# Alcohol_Detector_Project_Schematic.net
KiCad netlist of a schematic drawn in EAGLE
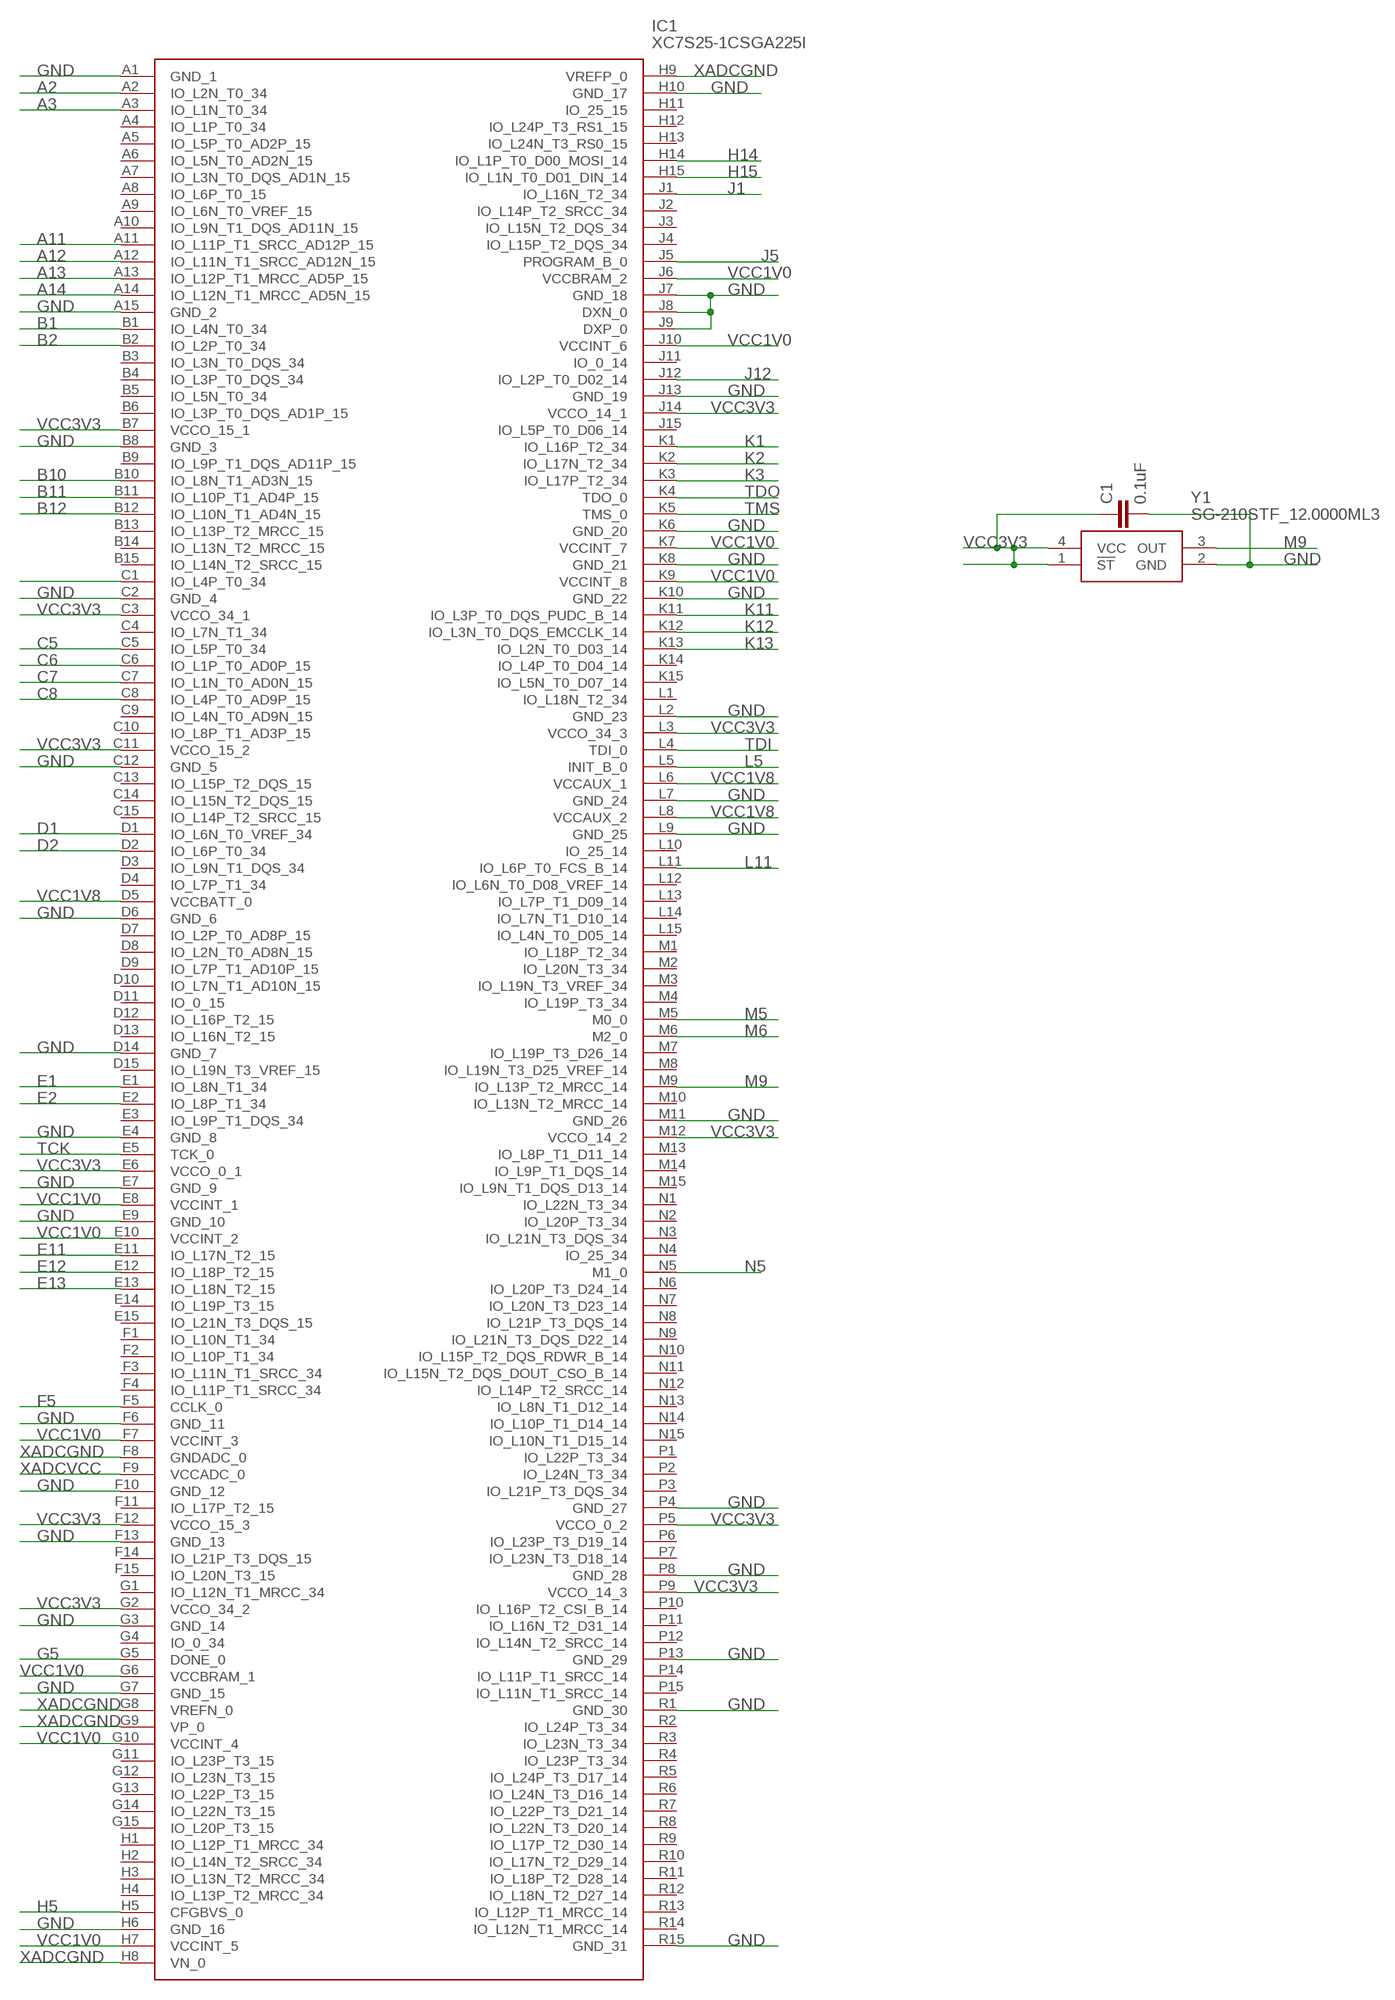
[diagram p0: schematic, sheet 1]
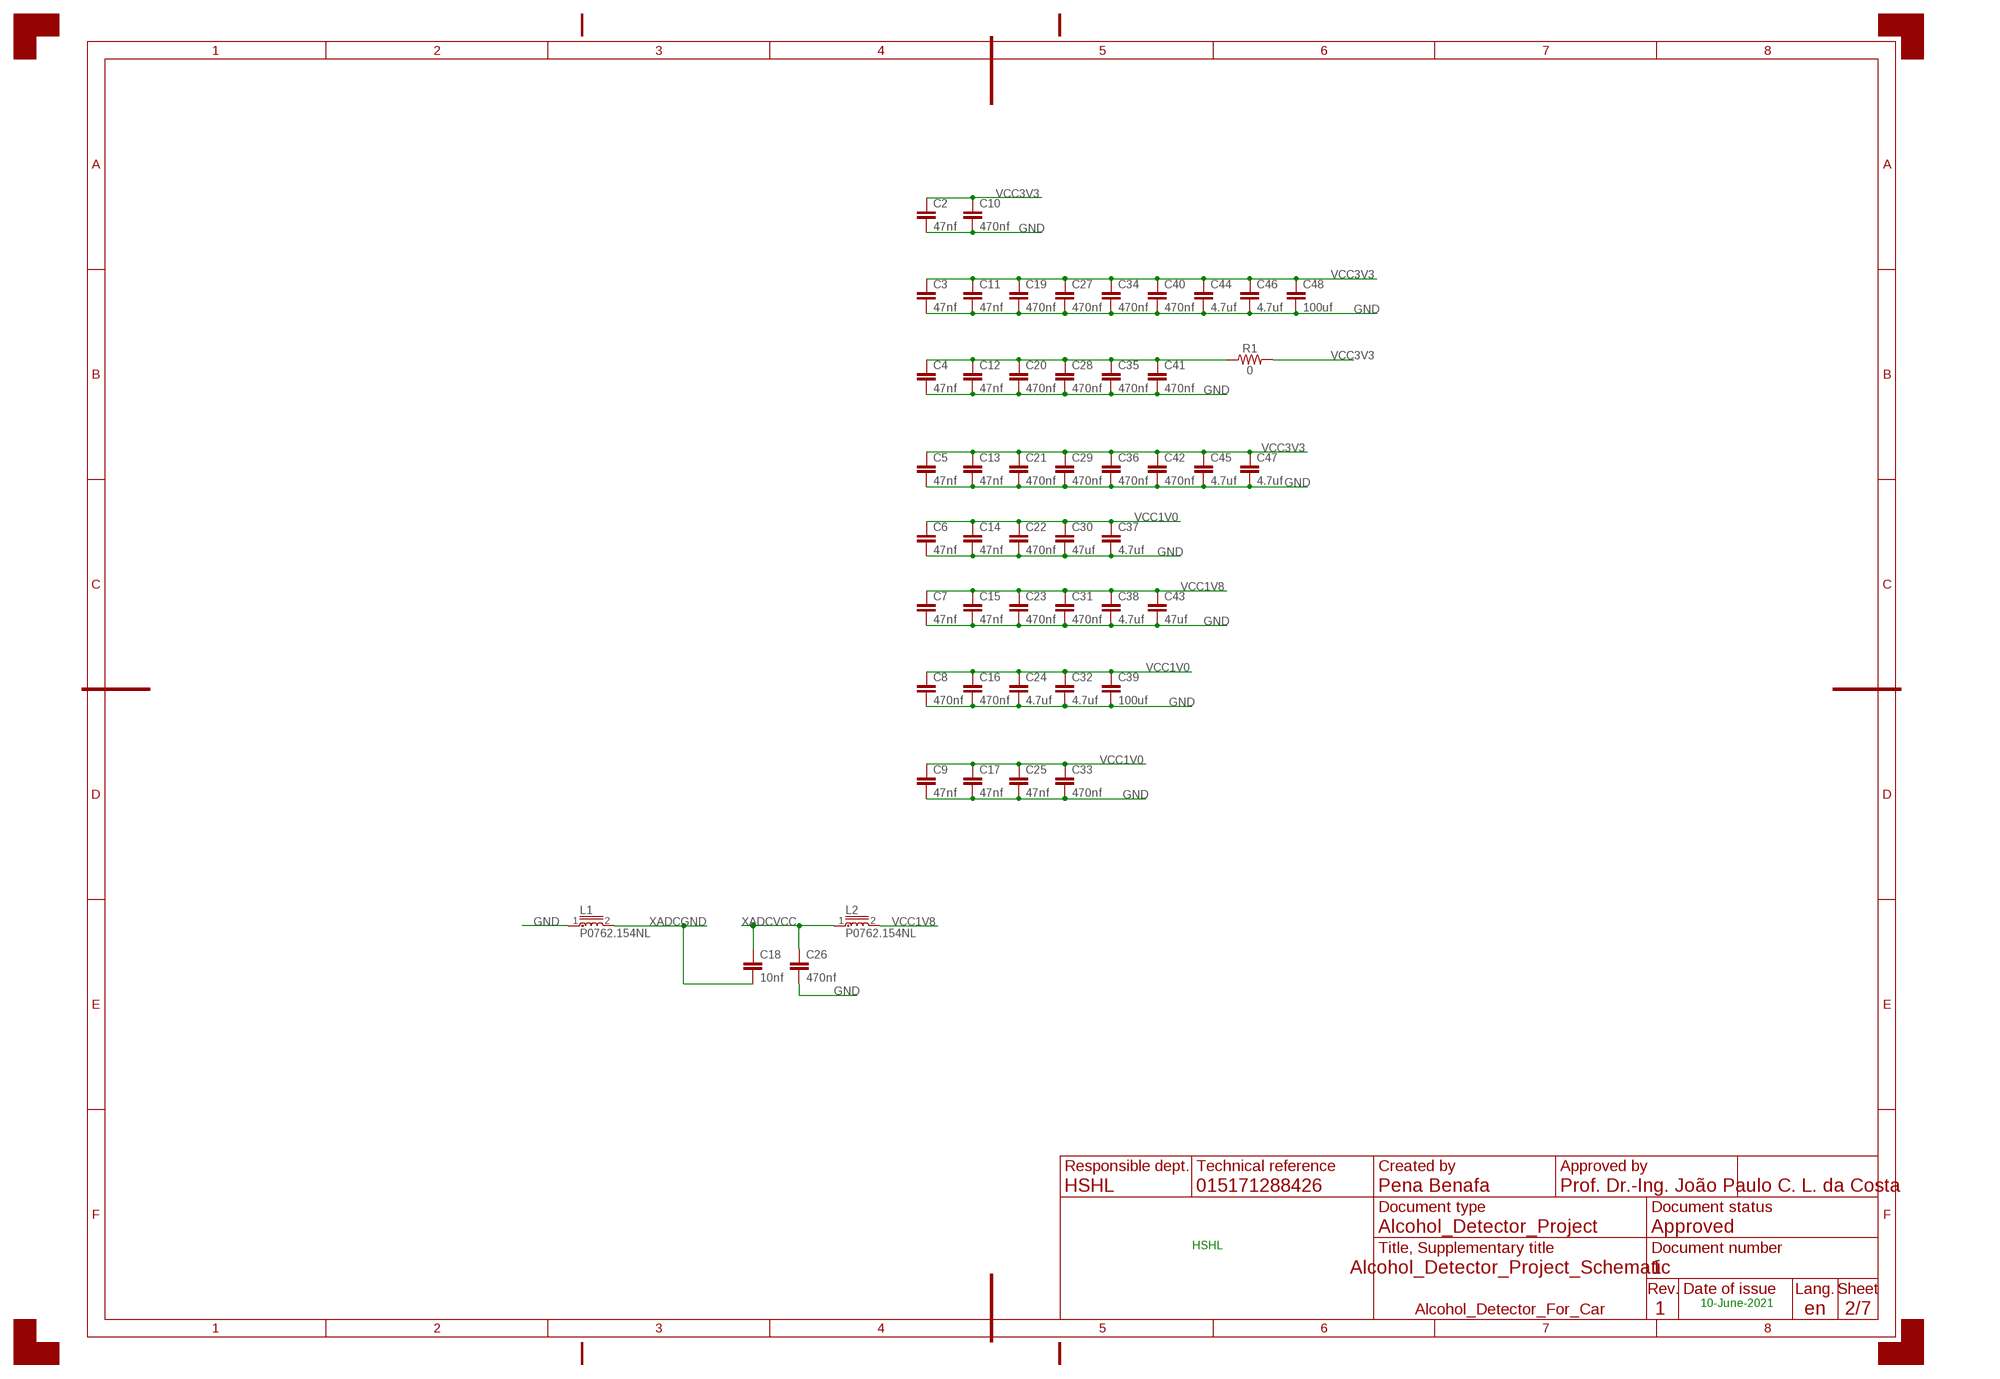
[diagram p1: schematic, sheet 2]
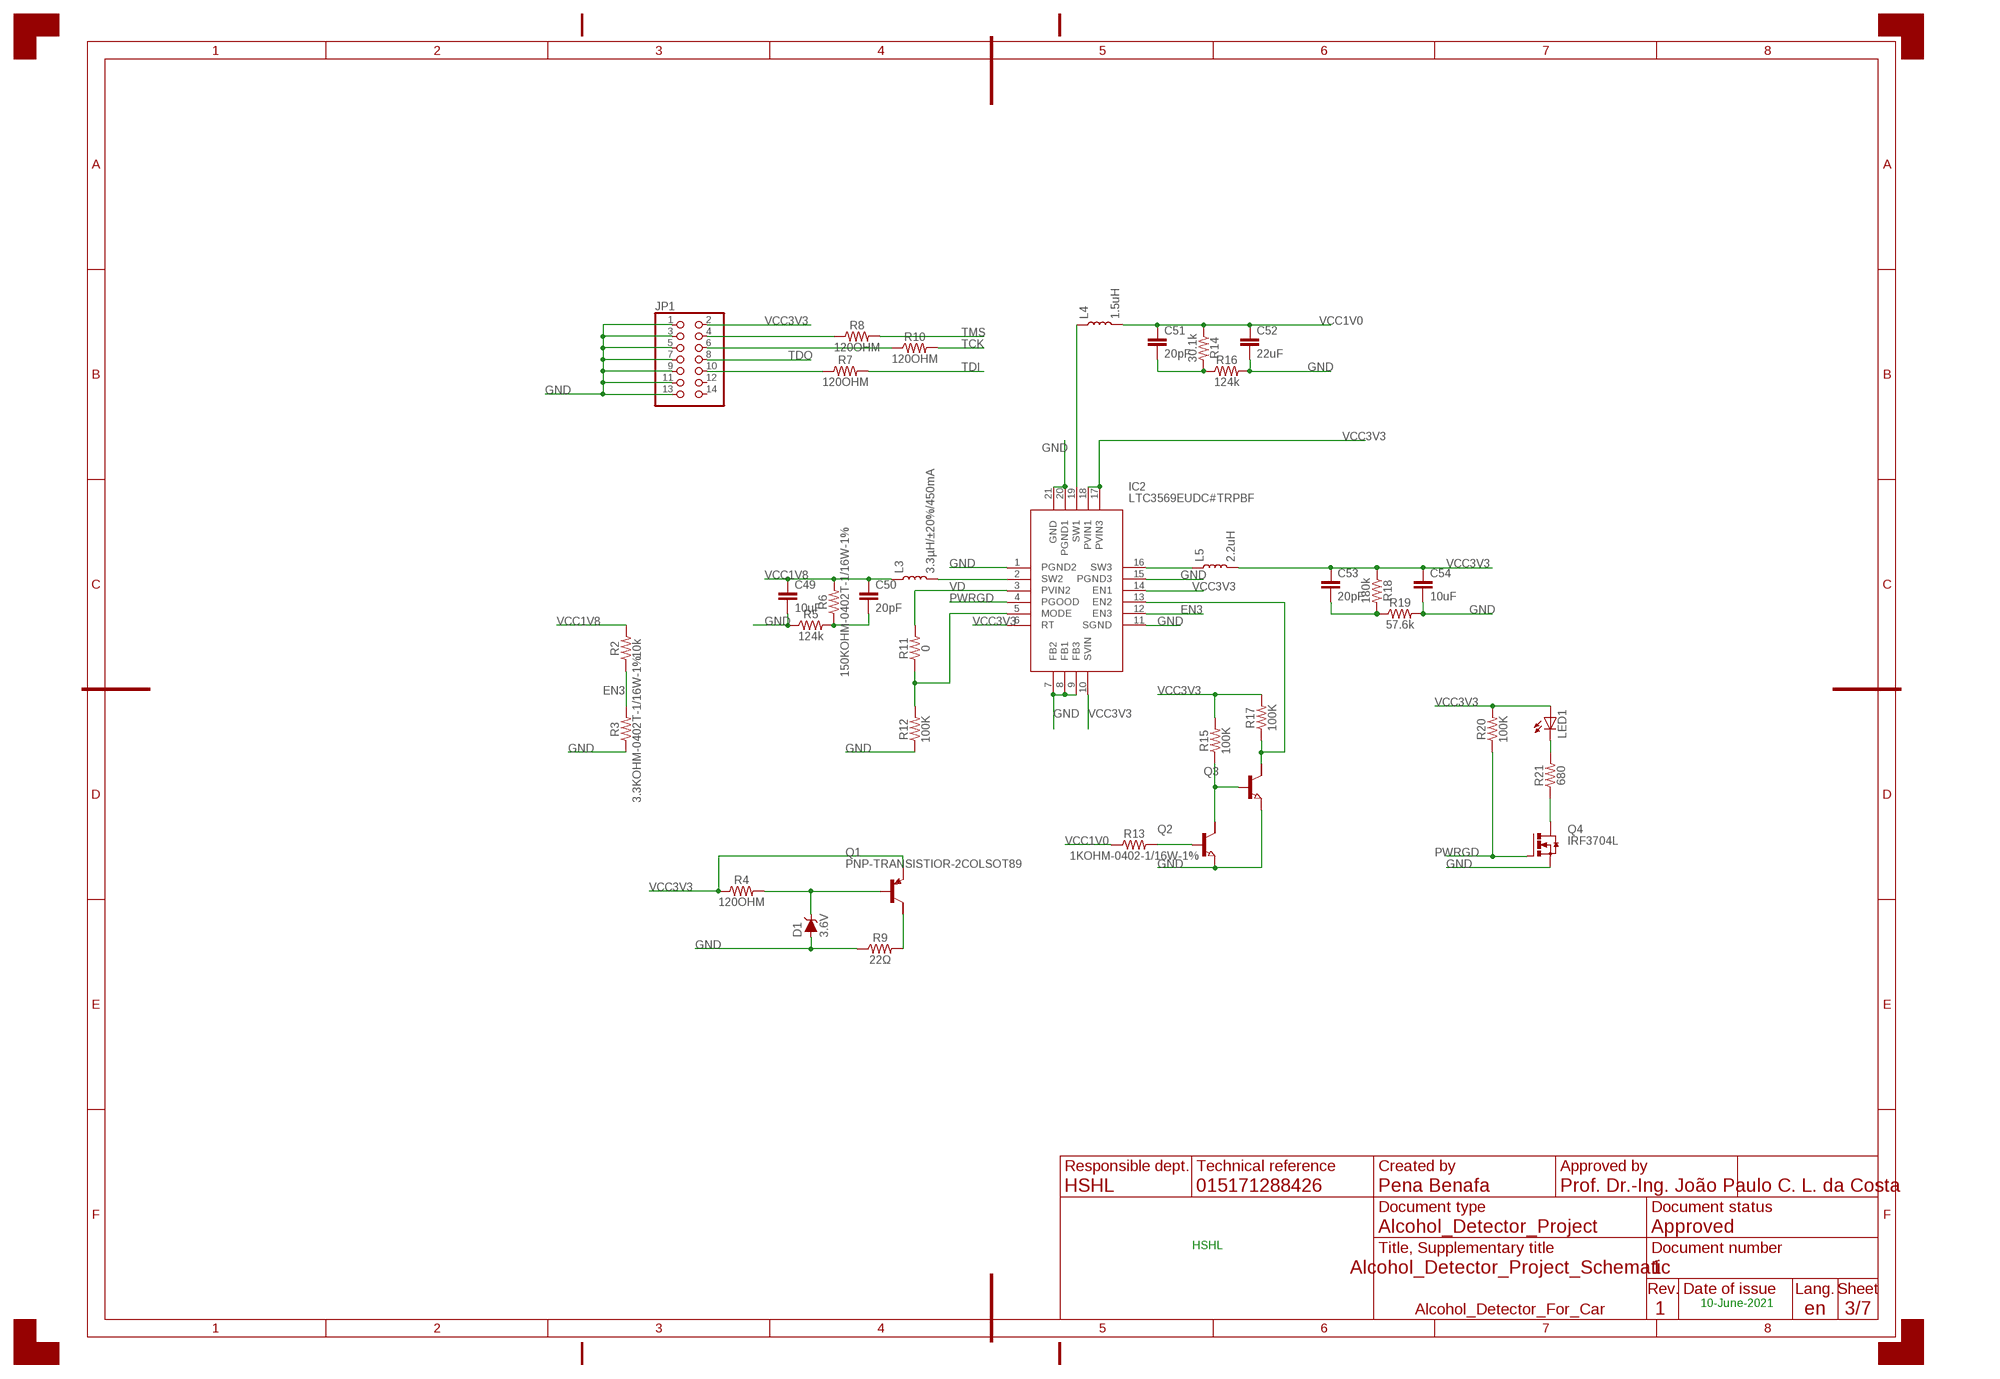
[diagram p2: schematic, sheet 3]
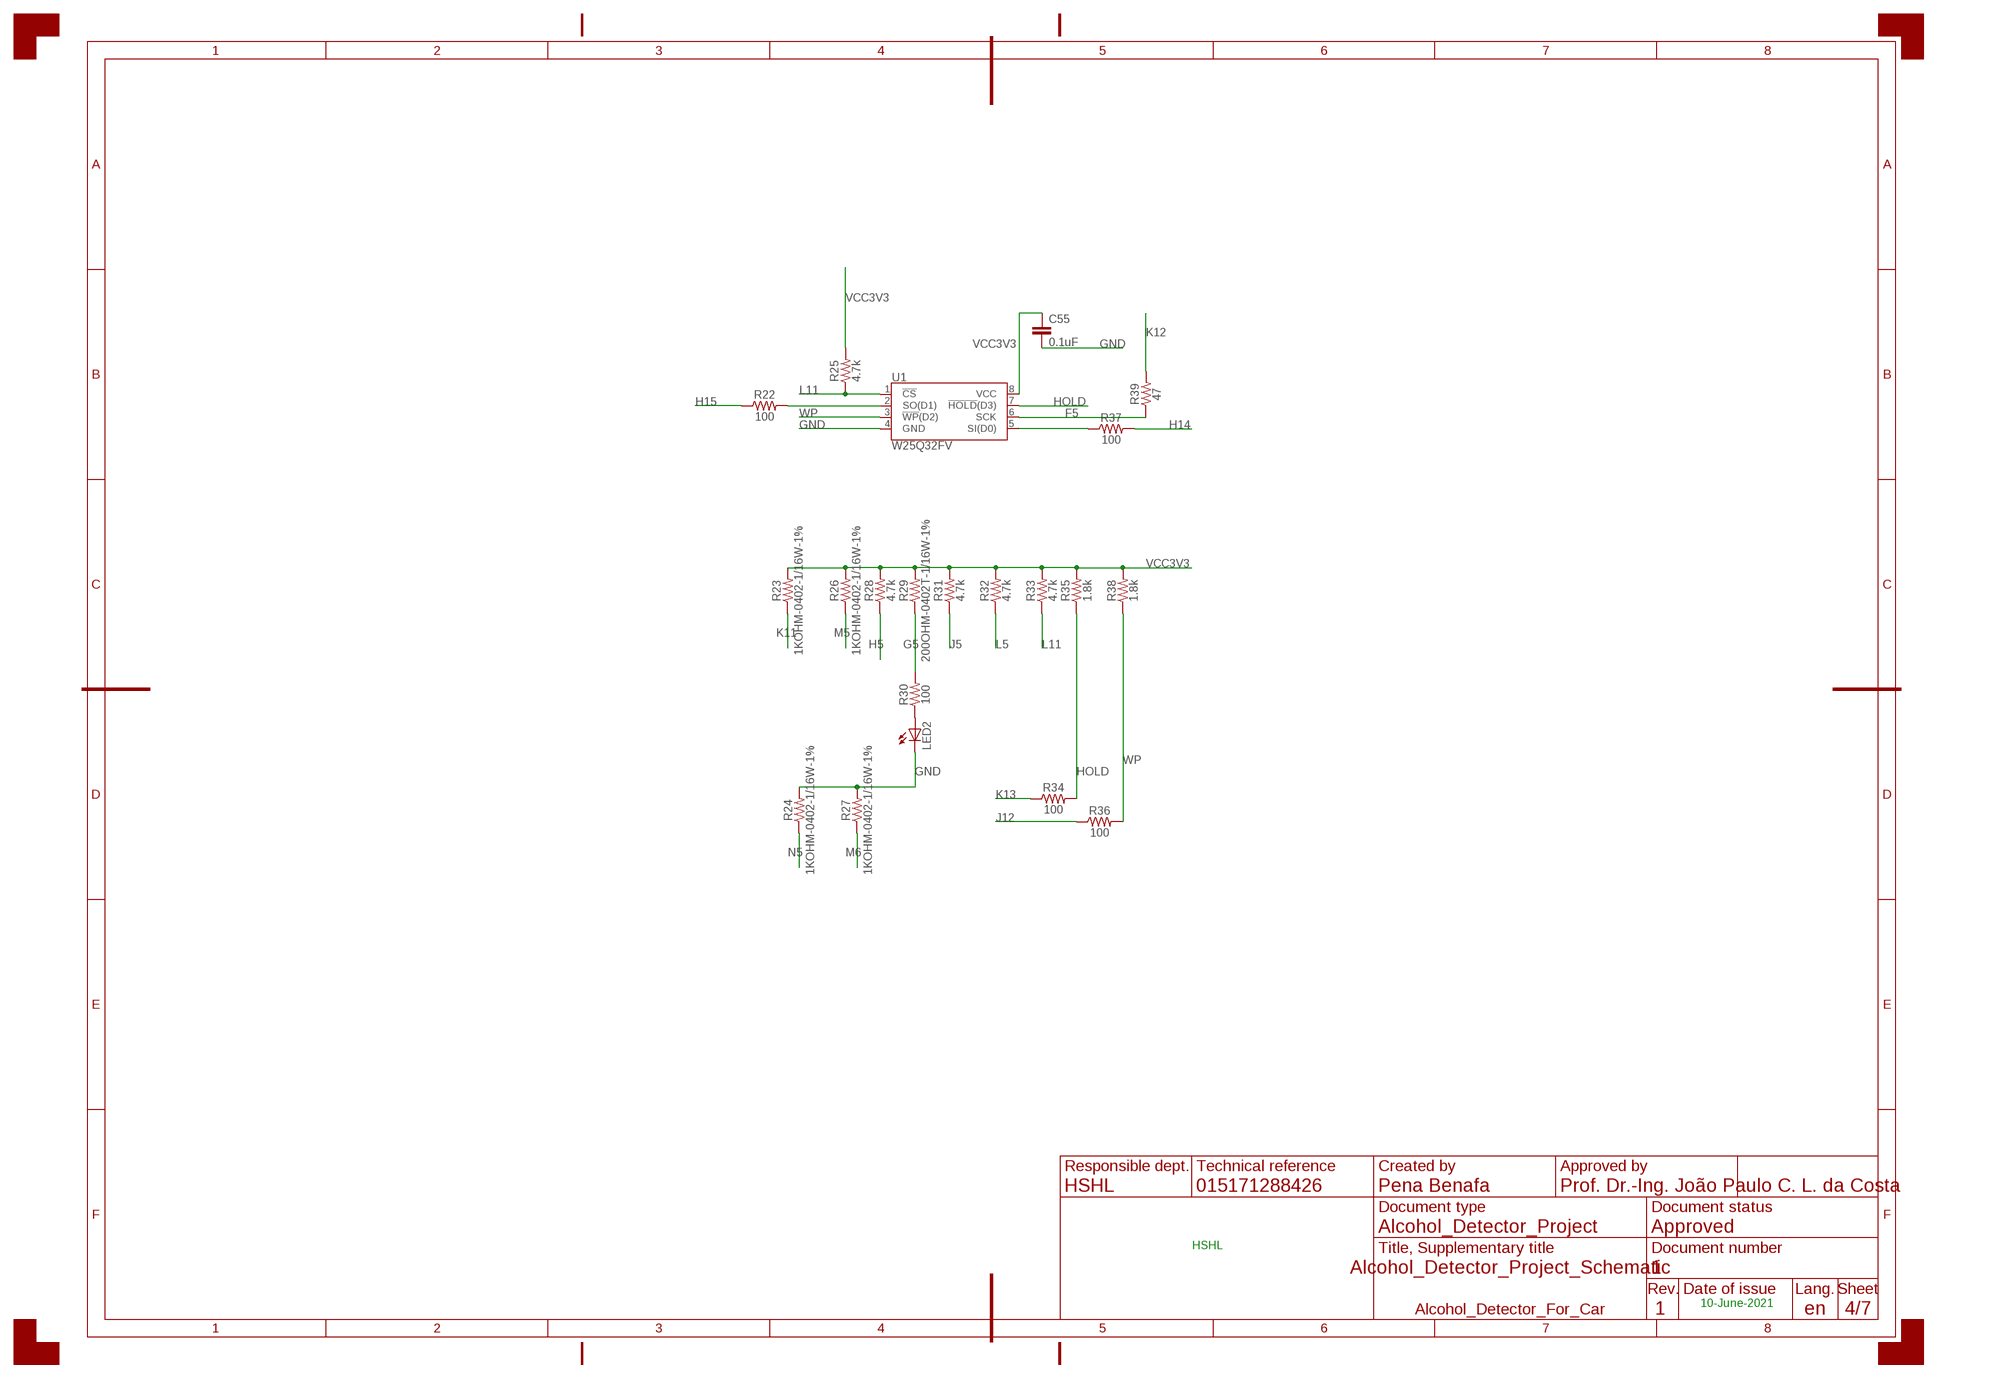
[diagram p3: schematic, sheet 4]
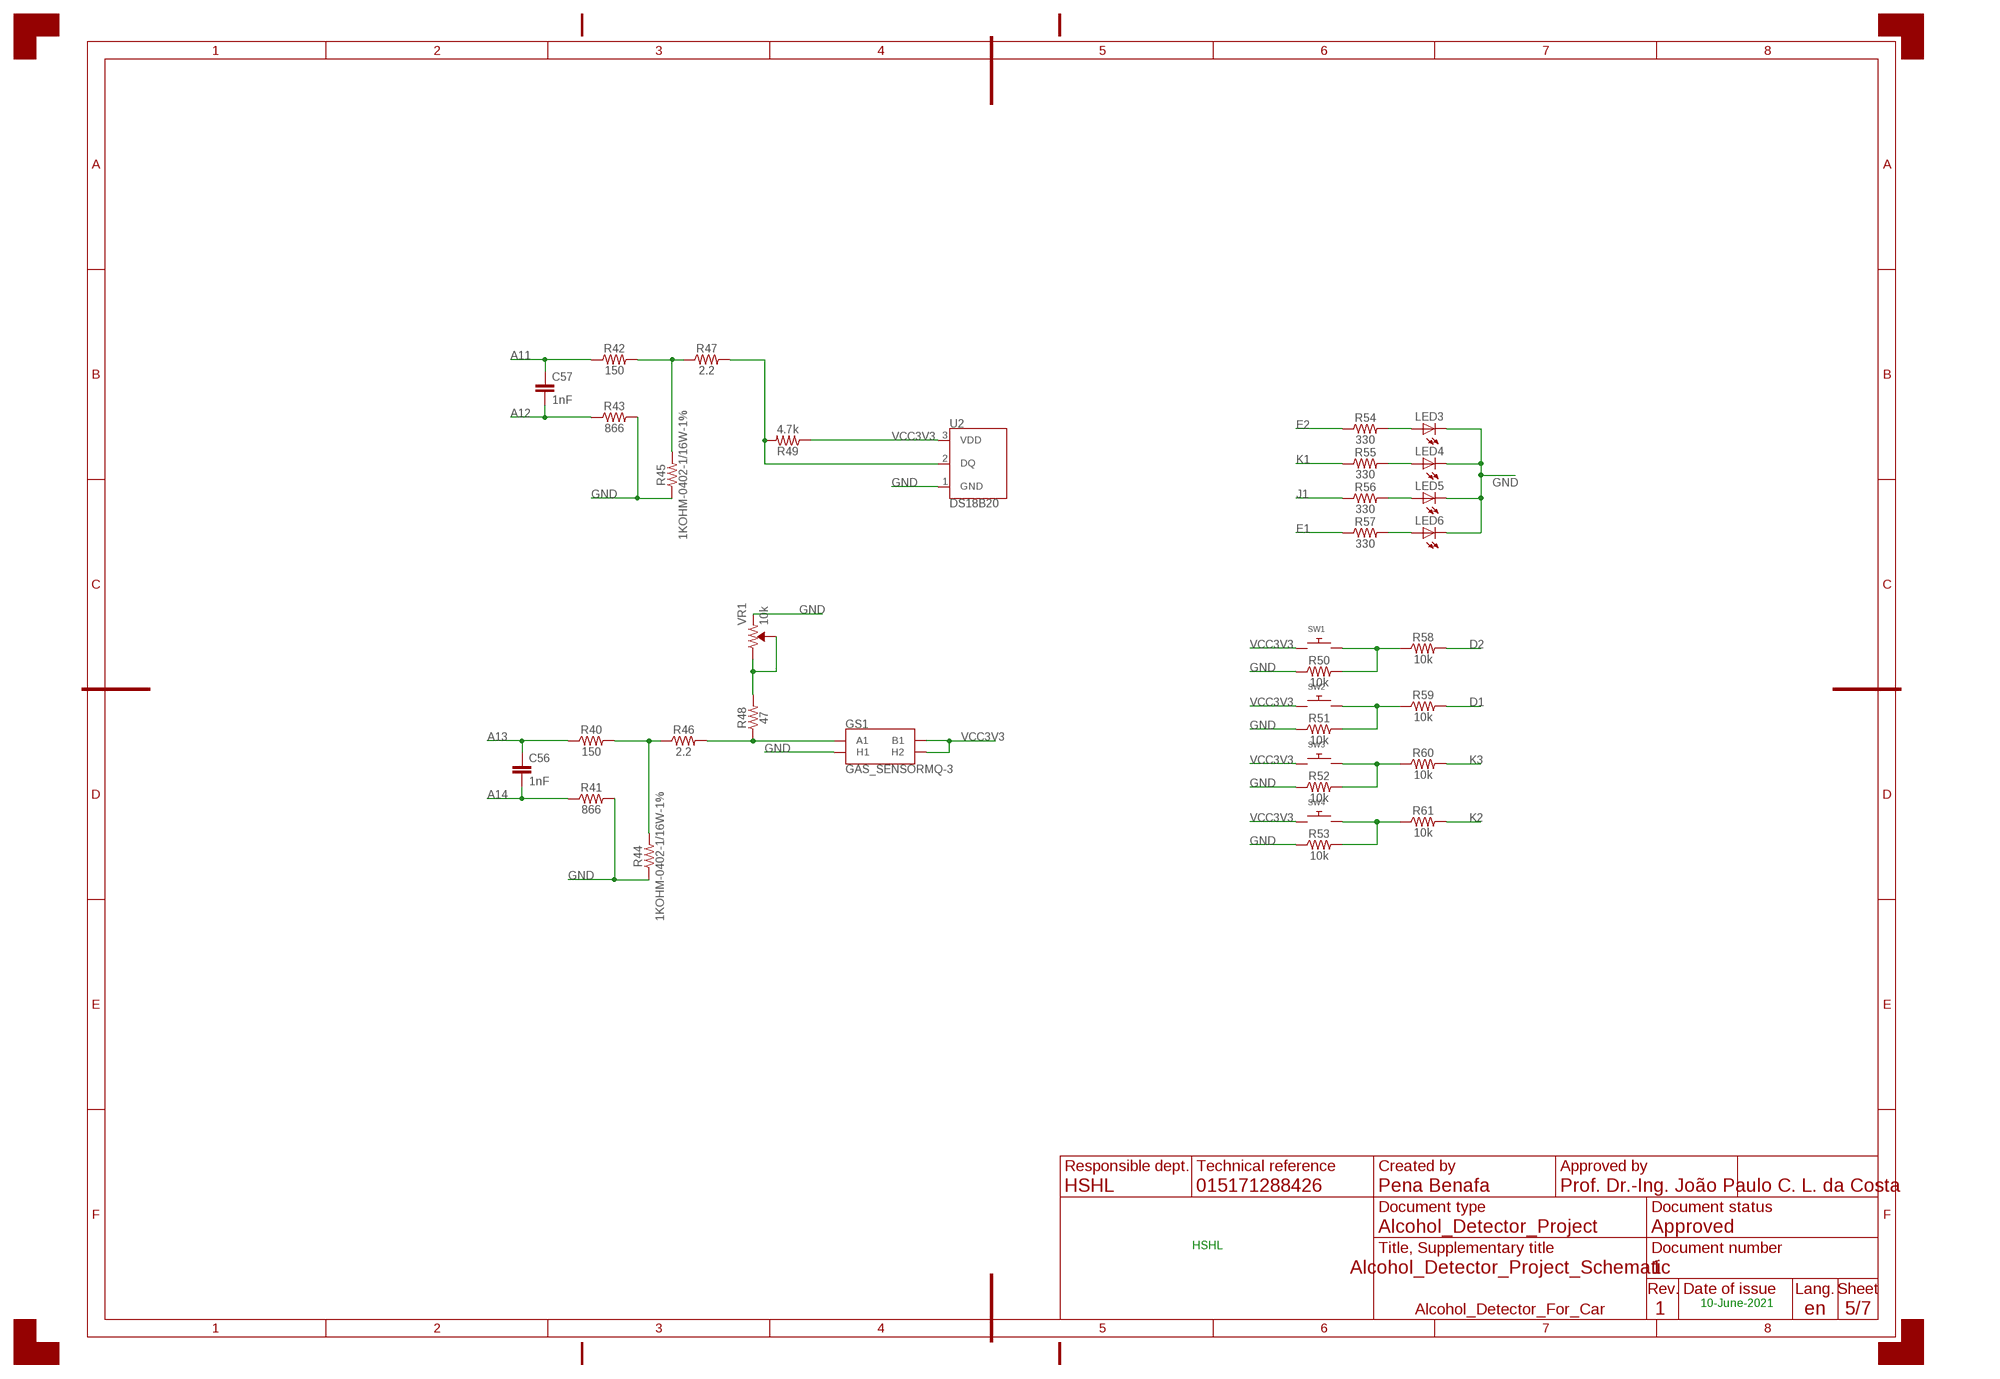
[diagram p4: schematic, sheet 5]
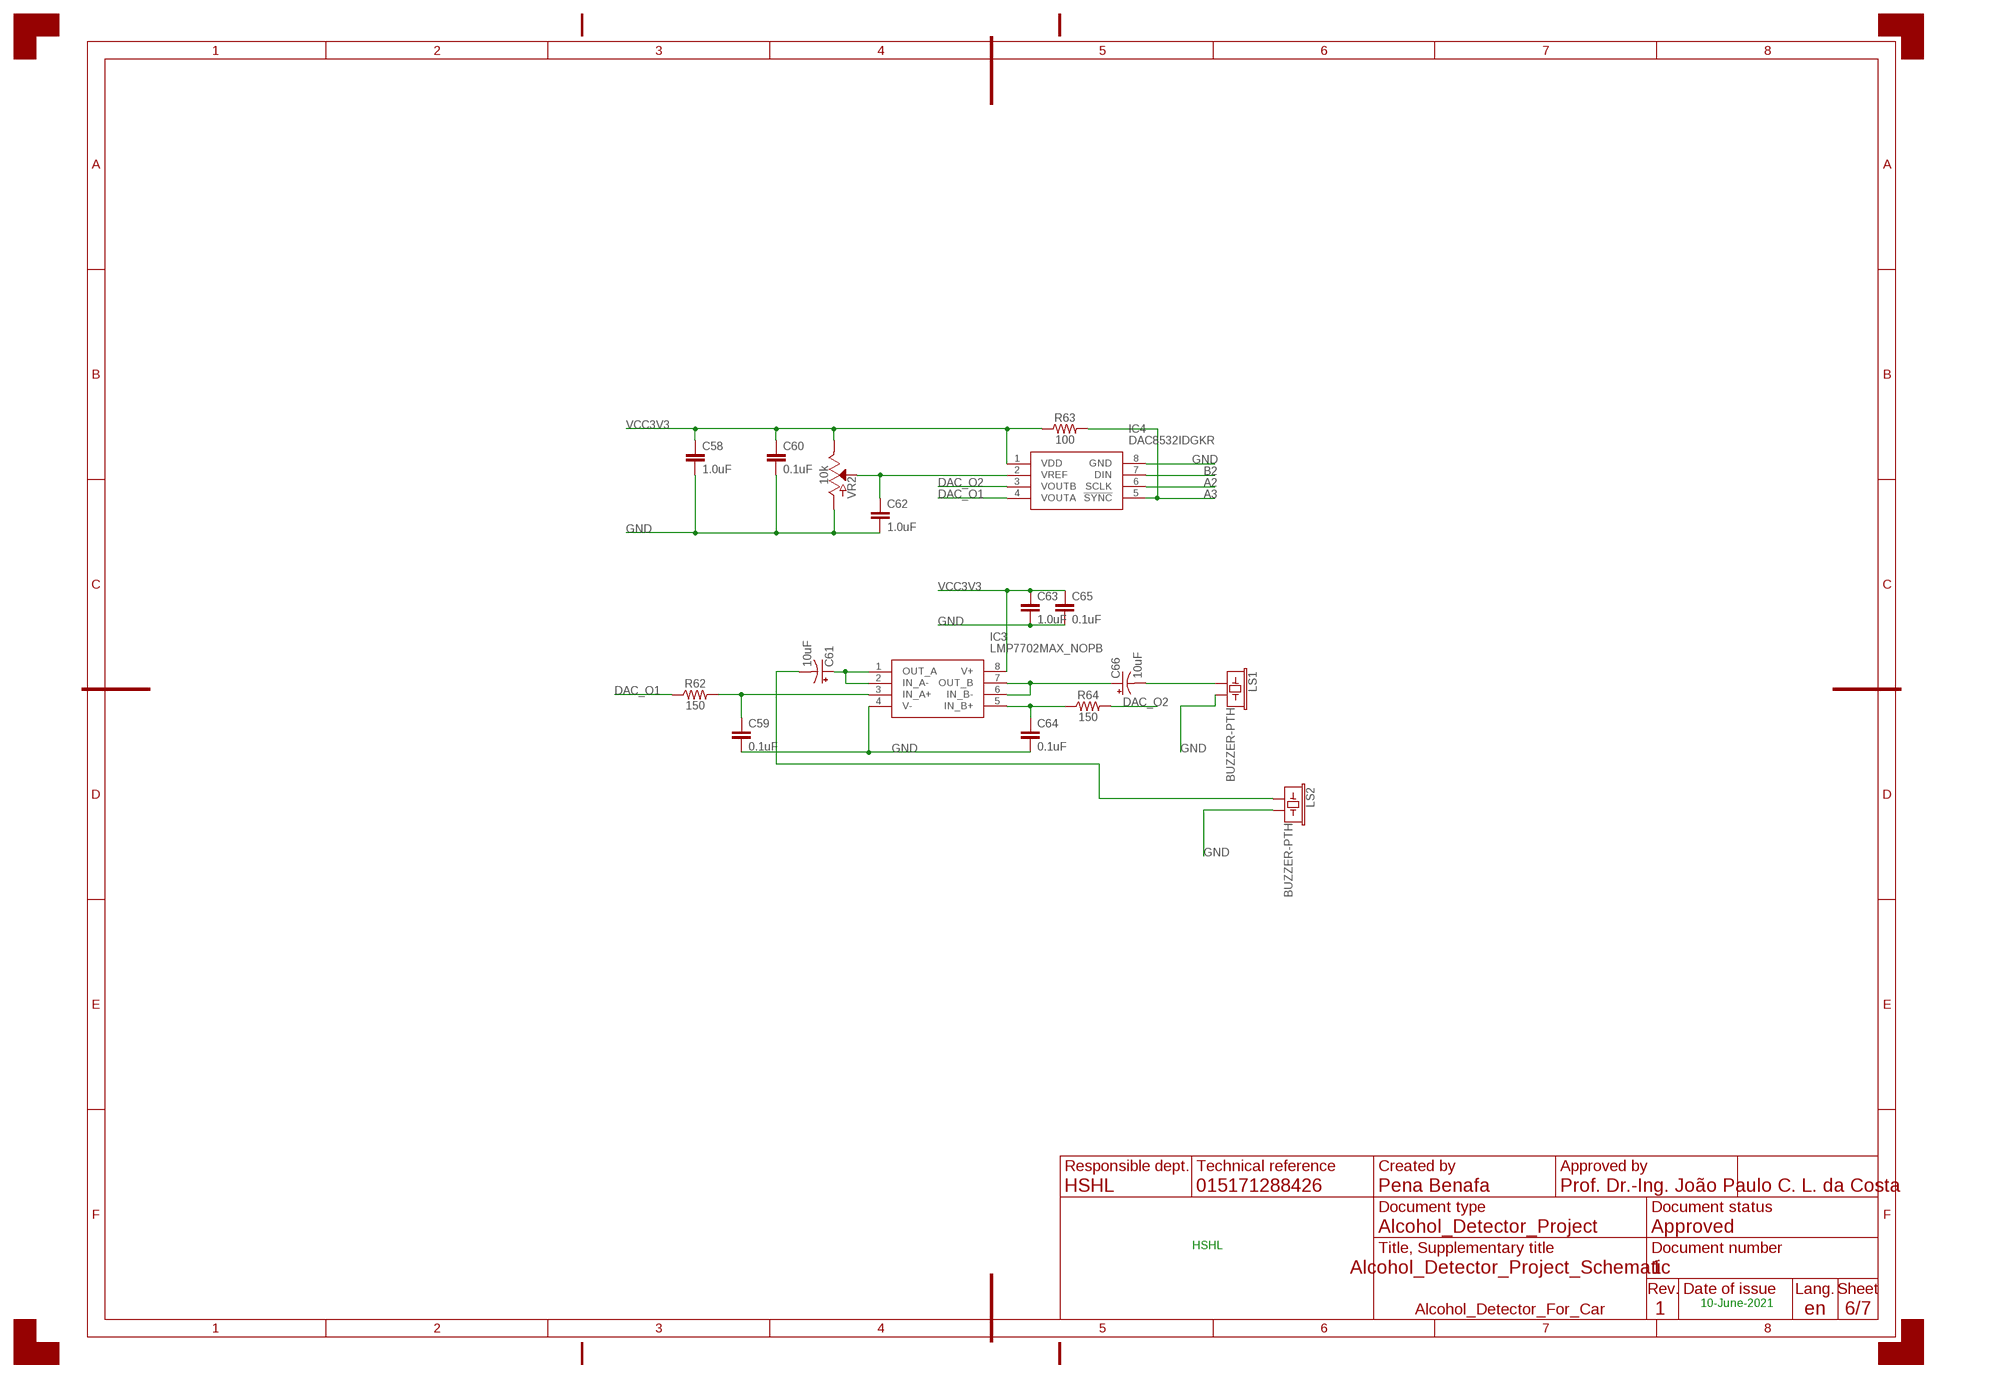
[diagram p5: schematic, sheet 6]
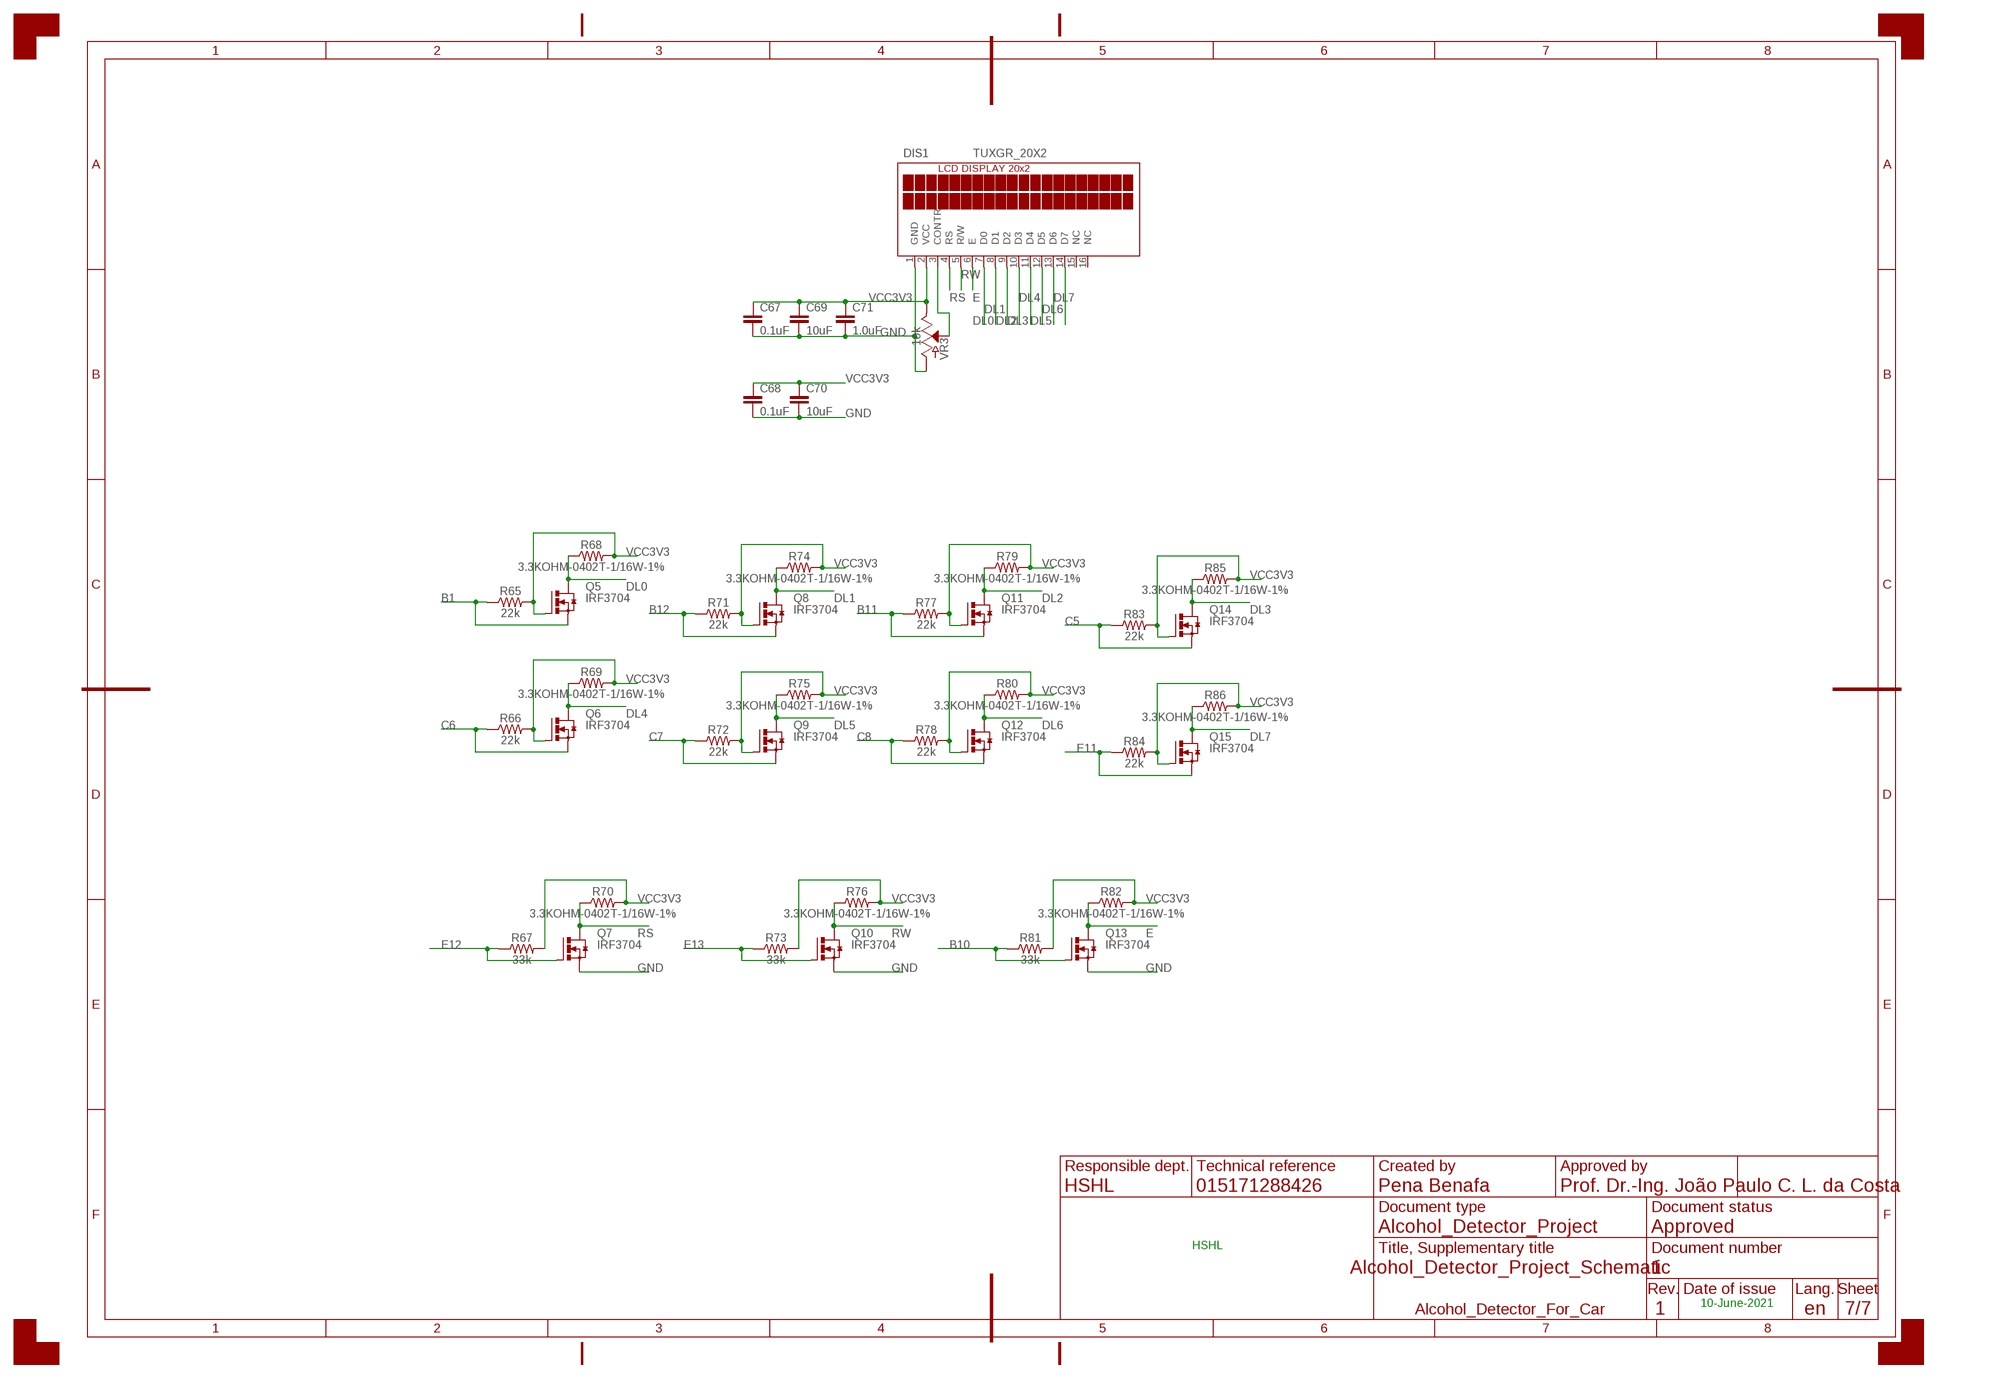
[diagram p6: schematic, sheet 7]

(export (version "E")
  (design (tool "Eeschema 10.0.6"))
  (components
    (comp (ref "C58")
      (value "1.0uF")
      (footprint "eagle-import:0402")
      (libsource (lib "eagle-import") (part "1.0UF-0402-16V-10%"))
    )
    (comp (ref "C59")
      (value "0.1uF")
      (footprint "eagle-import:0402")
      (libsource (lib "eagle-import") (part "0.1UF-0402-6.3V-10%-X7R"))
    )
    (comp (ref "C60")
      (value "0.1uF")
      (footprint "eagle-import:0402")
      (libsource (lib "eagle-import") (part "0.1UF-0402-6.3V-10%-X7R"))
    )
    (comp (ref "C61")
      (value "10uF")
      (footprint "eagle-import:0603-POLAR")
      (libsource (lib "eagle-import") (part "10UF-POLAR-0603-6.3V-20%(TANT)"))
    )
    (comp (ref "C62")
      (value "1.0uF")
      (footprint "eagle-import:0402")
      (libsource (lib "eagle-import") (part "1.0UF-0402-16V-10%"))
    )
    (comp (ref "C63")
      (value "1.0uF")
      (footprint "eagle-import:0402")
      (libsource (lib "eagle-import") (part "1.0UF-0402-16V-10%"))
    )
    (comp (ref "C64")
      (value "0.1uF")
      (footprint "eagle-import:0402")
      (libsource (lib "eagle-import") (part "0.1UF-0402-6.3V-10%-X7R"))
    )
    (comp (ref "C65")
      (value "0.1uF")
      (footprint "eagle-import:0402")
      (libsource (lib "eagle-import") (part "0.1UF-0402-6.3V-10%-X7R"))
    )
    (comp (ref "C66")
      (value "10uF")
      (footprint "eagle-import:0603-POLAR")
      (libsource (lib "eagle-import") (part "10UF-POLAR-0603-6.3V-20%(TANT)"))
    )
    (comp (ref "IC3")
      (value "LMP7702MAX_NOPB")
      (footprint "eagle-import:SOIC127P600X175-8N")
      (fields
        (field (name "MANUFACTURER_PART_NUMBER") "LMP7702MAX/NOPB")
        (field (name "MOUSER_PART_NUMBER") "926-LMP7702MAX/NOPB")
      )
      (libsource (lib "eagle-import") (part "LMP7702MAX_NOPB"))
    )
    (comp (ref "IC4")
      (value "DAC8532IDGKR")
      (footprint "eagle-import:SOP65P490X110-8N")
      (fields (field (name "MOUSER_PART_NUMBER") "595-DAC8532IDGKR"))
      (libsource (lib "eagle-import") (part "DAC8532IDGKR"))
    )
    (comp (ref "LS1")
      (value "BUZZER-PTH")
      (footprint "eagle-import:BUZZER-12MM")
      (libsource (lib "eagle-import") (part "BUZZER-PTH"))
    )
    (comp (ref "LS2")
      (value "BUZZER-PTH")
      (footprint "eagle-import:BUZZER-12MM")
      (libsource (lib "eagle-import") (part "BUZZER-PTH"))
    )
    (comp (ref "R62")
      (value "150")
      (footprint "eagle-import:0603")
      (libsource (lib "eagle-import") (part "150OHM-0603-1/10W-1%"))
    )
    (comp (ref "R63")
      (value "100")
      (footprint "eagle-import:0603")
      (libsource (lib "eagle-import") (part "100OHM-0603-1/10W-1%"))
    )
    (comp (ref "R64")
      (value "150")
      (footprint "eagle-import:0603")
      (libsource (lib "eagle-import") (part "150OHM-0603-1/10W-1%"))
    )
    (comp (ref "VR2")
      (value "10k")
      (footprint "eagle-import:SLIDER-SMALL")
      (libsource (lib "eagle-import") (part "POTENTIOMETER_SLIDE-20MM-1/10W-20%"))
    )
    (comp (ref "C56")
      (value "1nF")
      (footprint "eagle-import:0402")
      (libsource (lib "eagle-import") (part "1.0NF/1000PF-0402-25V-10%-X7R"))
    )
    (comp (ref "C57")
      (value "1nF")
      (footprint "eagle-import:0402")
      (libsource (lib "eagle-import") (part "1.0NF/1000PF-0402-25V-10%-X7R"))
    )
    (comp (ref "GS1")
      (value "GAS_SENSORMQ-3")
      (footprint "eagle-import:GAS_SENSOR")
      (libsource (lib "eagle-import") (part "GAS_SENSORMQ-3"))
    )
    (comp (ref "LED3")
      (value "LEDB152")
      (footprint "eagle-import:Q62902-B152")
      (libsource (lib "eagle-import") (part "LEDB152"))
    )
    (comp (ref "LED4")
      (value "LEDB152")
      (footprint "eagle-import:Q62902-B152")
      (libsource (lib "eagle-import") (part "LEDB152"))
    )
    (comp (ref "LED5")
      (value "LEDB152")
      (footprint "eagle-import:Q62902-B152")
      (libsource (lib "eagle-import") (part "LEDB152"))
    )
    (comp (ref "LED6")
      (value "LEDB152")
      (footprint "eagle-import:Q62902-B152")
      (libsource (lib "eagle-import") (part "LEDB152"))
    )
    (comp (ref "R40")
      (value "150")
      (footprint "eagle-import:0603")
      (libsource (lib "eagle-import") (part "150OHM-0603-1/10W-1%"))
    )
    (comp (ref "R41")
      (value "866")
      (footprint "eagle-import:0603")
      (libsource (lib "eagle-import") (part "866OHM-0603-1/10W-1%"))
    )
    (comp (ref "R42")
      (value "150")
      (footprint "eagle-import:0603")
      (libsource (lib "eagle-import") (part "150OHM-0603-1/10W-1%"))
    )
    (comp (ref "R43")
      (value "866")
      (footprint "eagle-import:0603")
      (libsource (lib "eagle-import") (part "866OHM-0603-1/10W-1%"))
    )
    (comp (ref "R44")
      (value "1KOHM-0402-1/16W-1%")
      (footprint "eagle-import:0402")
      (libsource (lib "eagle-import") (part "1KOHM-0402-1/16W-1%"))
    )
    (comp (ref "R45")
      (value "1KOHM-0402-1/16W-1%")
      (footprint "eagle-import:0402")
      (libsource (lib "eagle-import") (part "1KOHM-0402-1/16W-1%"))
    )
    (comp (ref "R46")
      (value "2.2")
      (footprint "eagle-import:0603")
      (libsource (lib "eagle-import") (part "2.2OHM-0603-1/10W-5%"))
    )
    (comp (ref "R47")
      (value "2.2")
      (footprint "eagle-import:0603")
      (libsource (lib "eagle-import") (part "2.2OHM-0603-1/10W-5%"))
    )
    (comp (ref "R48")
      (value "47")
      (footprint "eagle-import:0603")
      (libsource (lib "eagle-import") (part "47OHM-0603-1/10W-1%"))
    )
    (comp (ref "R49")
      (value "4.7k")
      (footprint "eagle-import:0402-TIGHT")
      (libsource (lib "eagle-import") (part "4.7KOHM-0402T-1/16W-1%"))
    )
    (comp (ref "R50")
      (value "10k")
      (footprint "eagle-import:0402")
      (libsource (lib "eagle-import") (part "10KOHM-0402-1/16W-1%"))
    )
    (comp (ref "R51")
      (value "10k")
      (footprint "eagle-import:0402")
      (libsource (lib "eagle-import") (part "10KOHM-0402-1/16W-1%"))
    )
    (comp (ref "R52")
      (value "10k")
      (footprint "eagle-import:0402")
      (libsource (lib "eagle-import") (part "10KOHM-0402-1/16W-1%"))
    )
    (comp (ref "R53")
      (value "10k")
      (footprint "eagle-import:0402")
      (libsource (lib "eagle-import") (part "10KOHM-0402-1/16W-1%"))
    )
    (comp (ref "R54")
      (value "330")
      (footprint "eagle-import:0402")
      (libsource (lib "eagle-import") (part "330OHM-0402-1/16W-5%"))
    )
    (comp (ref "R55")
      (value "330")
      (footprint "eagle-import:0402")
      (libsource (lib "eagle-import") (part "330OHM-0402-1/16W-5%"))
    )
    (comp (ref "R56")
      (value "330")
      (footprint "eagle-import:0402")
      (libsource (lib "eagle-import") (part "330OHM-0402-1/16W-5%"))
    )
    (comp (ref "R57")
      (value "330")
      (footprint "eagle-import:0402")
      (libsource (lib "eagle-import") (part "330OHM-0402-1/16W-5%"))
    )
    (comp (ref "R58")
      (value "10k")
      (footprint "eagle-import:0402")
      (libsource (lib "eagle-import") (part "10KOHM-0402-1/16W-1%"))
    )
    (comp (ref "R59")
      (value "10k")
      (footprint "eagle-import:0402")
      (libsource (lib "eagle-import") (part "10KOHM-0402-1/16W-1%"))
    )
    (comp (ref "R60")
      (value "10k")
      (footprint "eagle-import:0402")
      (libsource (lib "eagle-import") (part "10KOHM-0402-1/16W-1%"))
    )
    (comp (ref "R61")
      (value "10k")
      (footprint "eagle-import:0402")
      (libsource (lib "eagle-import") (part "10KOHM-0402-1/16W-1%"))
    )
    (comp (ref "SW1")
      (value "SWITCH_PUSHBUTTONC&K_KSS")
      (footprint "eagle-import:BTN_CK_KSS")
      (libsource (lib "eagle-import") (part "SWITCH_PUSHBUTTONC&K_KSS"))
    )
    (comp (ref "SW2")
      (value "SWITCH_PUSHBUTTONC&K_KSS")
      (footprint "eagle-import:BTN_CK_KSS")
      (libsource (lib "eagle-import") (part "SWITCH_PUSHBUTTONC&K_KSS"))
    )
    (comp (ref "SW3")
      (value "SWITCH_PUSHBUTTONC&K_KSS")
      (footprint "eagle-import:BTN_CK_KSS")
      (libsource (lib "eagle-import") (part "SWITCH_PUSHBUTTONC&K_KSS"))
    )
    (comp (ref "SW4")
      (value "SWITCH_PUSHBUTTONC&K_KSS")
      (footprint "eagle-import:BTN_CK_KSS")
      (libsource (lib "eagle-import") (part "SWITCH_PUSHBUTTONC&K_KSS"))
    )
    (comp (ref "U2")
      (value "DS18B20")
      (footprint "eagle-import:TO-92-AMMO")
      (libsource (lib "eagle-import") (part "DS18B20"))
    )
    (comp (ref "VR1")
      (value "10k")
      (footprint "eagle-import:TRIMPOT-PTH-3386U")
      (libsource (lib "eagle-import") (part "TRIMPOT-PTH-10MM-KNOB-1/2W-10%"))
    )
    (comp (ref "C49")
      (value "10uF")
      (footprint "eagle-import:0402-TIGHT")
      (libsource (lib "eagle-import") (part "10UF-0402T-6.3V-20%"))
    )
    (comp (ref "C50")
      (value "20pF")
      (footprint "eagle-import:0402-TIGHT")
      (libsource (lib "eagle-import") (part "20PF-0402T-50V-5%"))
    )
    (comp (ref "C51")
      (value "20pF")
      (footprint "eagle-import:0402-TIGHT")
      (libsource (lib "eagle-import") (part "20PF-0402T-50V-5%"))
    )
    (comp (ref "C52")
      (value "22uF")
      (footprint "eagle-import:0603")
      (libsource (lib "eagle-import") (part "22UF-0603-6.3V-20%"))
    )
    (comp (ref "C53")
      (value "20pF")
      (footprint "eagle-import:0402-TIGHT")
      (libsource (lib "eagle-import") (part "20PF-0402T-50V-5%"))
    )
    (comp (ref "C54")
      (value "10uF")
      (footprint "eagle-import:0402-TIGHT")
      (libsource (lib "eagle-import") (part "10UF-0402T-6.3V-20%"))
    )
    (comp (ref "D1")
      (value "3.6V")
      (footprint "eagle-import:SOD-323")
      (libsource (lib "eagle-import") (part "DIODE-ZENER-BZT52C3V6S"))
    )
    (comp (ref "IC2")
      (value "LTC3569EUDC#TRPBF")
      (footprint "eagle-import:QFN50P300X400X80-21N")
      (libsource (lib "eagle-import") (part "LTC3569EUDC#TRPBF"))
    )
    (comp (ref "JP1")
      (value "PINHD-2X7/90")
      (footprint "eagle-import:2X07_90")
      (libsource (lib "eagle-import") (part "PINHD-2X7/90"))
    )
    (comp (ref "L3")
      (value "3.3µH/±20%/450mA")
      (footprint "eagle-import:0805")
      (libsource (lib "eagle-import") (part "INDUCTOR-0805-3.3UH"))
    )
    (comp (ref "L4")
      (value "1.5uH")
      (footprint "eagle-import:INDUCTOR_2X2")
      (libsource (lib "eagle-import") (part "1.5UH-2X2-1.4A"))
    )
    (comp (ref "L5")
      (value "2.2uH")
      (footprint "eagle-import:0805-WIDE")
      (libsource (lib "eagle-import") (part "INDUCTOR-0805_WIDE-2.2UH"))
    )
    (comp (ref "LED1")
      (value "LEDB152")
      (footprint "eagle-import:Q62902-B152")
      (libsource (lib "eagle-import") (part "LEDB152"))
    )
    (comp (ref "Q1")
      (value "PNP-TRANSISTIOR-2COLSOT89")
      (footprint "eagle-import:SOT89")
      (libsource (lib "eagle-import") (part "PNP-TRANSISTIOR-2COLSOT89"))
    )
    (comp (ref "Q2")
      (value "NPN-TRANSISTIOR-2COLSOT89")
      (footprint "eagle-import:SOT89")
      (libsource (lib "eagle-import") (part "NPN-TRANSISTIOR-2COLSOT89"))
    )
    (comp (ref "Q3")
      (value "NPN-TRANSISTIOR-2COLSOT89")
      (footprint "eagle-import:SOT89")
      (libsource (lib "eagle-import") (part "NPN-TRANSISTIOR-2COLSOT89"))
    )
    (comp (ref "Q4")
      (value "IRF3704L")
      (footprint "eagle-import:TO262-H")
      (libsource (lib "eagle-import") (part "IRF3704L"))
    )
    (comp (ref "R2")
      (value "10k")
      (footprint "eagle-import:0402-TIGHT")
      (libsource (lib "eagle-import") (part "10KOHM-0402T-1/16W-1%"))
    )
    (comp (ref "R3")
      (value "3.3KOHM-0402T-1/16W-1%")
      (footprint "eagle-import:0402-TIGHT")
      (libsource (lib "eagle-import") (part "3.3KOHM-0402T-1/16W-1%"))
    )
    (comp (ref "R4")
      (value "120OHM")
      (footprint "eagle-import:0603")
      (libsource (lib "eagle-import") (part "120OHM"))
    )
    (comp (ref "R5")
      (value "124k")
      (footprint "eagle-import:0603")
      (libsource (lib "eagle-import") (part "124KOHM"))
    )
    (comp (ref "R6")
      (value "150KOHM-0402T-1/16W-1%")
      (footprint "eagle-import:0402-TIGHT")
      (libsource (lib "eagle-import") (part "150KOHM-0402T-1/16W-1%"))
    )
    (comp (ref "R7")
      (value "120OHM")
      (footprint "eagle-import:0603")
      (libsource (lib "eagle-import") (part "120OHM"))
    )
    (comp (ref "R8")
      (value "120OHM")
      (footprint "eagle-import:0603")
      (libsource (lib "eagle-import") (part "120OHM"))
    )
    (comp (ref "R9")
      (value "22Ω")
      (footprint "eagle-import:0402")
      (libsource (lib "eagle-import") (part "22OHM-0402-1/10W-1%"))
    )
    (comp (ref "R10")
      (value "120OHM")
      (footprint "eagle-import:0603")
      (libsource (lib "eagle-import") (part "120OHM"))
    )
    (comp (ref "R11")
      (value "0")
      (footprint "eagle-import:0402")
      (libsource (lib "eagle-import") (part "0OHM-0402-1/10W"))
    )
    (comp (ref "R12")
      (value "100K")
      (footprint "eagle-import:0402")
      (libsource (lib "eagle-import") (part "100KOHM-0402-1/16W-1%"))
    )
    (comp (ref "R13")
      (value "1KOHM-0402-1/16W-1%")
      (footprint "eagle-import:0402")
      (libsource (lib "eagle-import") (part "1KOHM-0402-1/16W-1%"))
    )
    (comp (ref "R14")
      (value "30.1k")
      (footprint "eagle-import:0603")
      (libsource (lib "eagle-import") (part "30.1KOHM-0603-1/10W-1%"))
    )
    (comp (ref "R15")
      (value "100K")
      (footprint "eagle-import:0402")
      (libsource (lib "eagle-import") (part "100KOHM-0402-1/16W-1%"))
    )
    (comp (ref "R16")
      (value "124k")
      (footprint "eagle-import:0603")
      (libsource (lib "eagle-import") (part "124KOHM"))
    )
    (comp (ref "R17")
      (value "100K")
      (footprint "eagle-import:0402")
      (libsource (lib "eagle-import") (part "100KOHM-0402-1/16W-1%"))
    )
    (comp (ref "R18")
      (value "180k")
      (footprint "eagle-import:0603")
      (libsource (lib "eagle-import") (part "180KOHM-0603-1/10W-1%"))
    )
    (comp (ref "R19")
      (value "57.6k")
      (footprint "eagle-import:0603")
      (libsource (lib "eagle-import") (part "57.6KOHM"))
    )
    (comp (ref "R20")
      (value "100K")
      (footprint "eagle-import:0402")
      (libsource (lib "eagle-import") (part "100KOHM-0402-1/16W-1%"))
    )
    (comp (ref "R21")
      (value "680")
      (footprint "eagle-import:0603")
      (libsource (lib "eagle-import") (part "680OHM-0603-1/10W-5%"))
    )
    (comp (ref "C1")
      (value "0.1uF")
      (footprint "eagle-import:0402")
      (libsource (lib "eagle-import") (part "0.1UF-0402-6.3V-10%-X7R"))
    )
    (comp (ref "IC1")
      (value "XC7S25-1CSGA225I")
      (footprint "eagle-import:BGA225C80P15X15_1300X1300X140")
      (libsource (lib "eagle-import") (part "XC7S25-1CSGA225I"))
    )
    (comp (ref "Y1")
      (value "SG-210STF_12.0000ML3")
      (footprint "eagle-import:SG210STF120000ML3")
      (fields
        (field (name "MANUFACTURER_PART_NUMBER") "SG-210STF 12.0000ML3")
        (field (name "MOUSER_PART_NUMBER") "732-SG210STF12.0L3")
      )
      (libsource (lib "eagle-import") (part "SG-210STF_12.0000ML3"))
    )
    (comp (ref "C67")
      (value "0.1uF")
      (footprint "eagle-import:0402")
      (libsource (lib "eagle-import") (part "0.1UF-0402-6.3V-10%-X7R"))
    )
    (comp (ref "C68")
      (value "0.1uF")
      (footprint "eagle-import:0402")
      (libsource (lib "eagle-import") (part "0.1UF-0402-6.3V-10%-X7R"))
    )
    (comp (ref "C69")
      (value "10uF")
      (footprint "eagle-import:0402-TIGHT")
      (libsource (lib "eagle-import") (part "10UF-0402T-6.3V-20%"))
    )
    (comp (ref "C70")
      (value "10uF")
      (footprint "eagle-import:0402-TIGHT")
      (libsource (lib "eagle-import") (part "10UF-0402T-6.3V-20%"))
    )
    (comp (ref "C71")
      (value "1.0uF")
      (footprint "eagle-import:0402")
      (libsource (lib "eagle-import") (part "1.0UF-0402-16V-10%"))
    )
    (comp (ref "DIS1")
      (value "TUXGR_20X2")
      (footprint "eagle-import:TUXGR_20X2")
      (libsource (lib "eagle-import") (part "TUXGR_20X2"))
    )
    (comp (ref "Q5")
      (value "IRF3704")
      (footprint "eagle-import:TO220AH")
      (libsource (lib "eagle-import") (part "IRF3704"))
    )
    (comp (ref "Q6")
      (value "IRF3704")
      (footprint "eagle-import:TO220AH")
      (libsource (lib "eagle-import") (part "IRF3704"))
    )
    (comp (ref "Q7")
      (value "IRF3704")
      (footprint "eagle-import:TO220AH")
      (libsource (lib "eagle-import") (part "IRF3704"))
    )
    (comp (ref "Q8")
      (value "IRF3704")
      (footprint "eagle-import:TO220AH")
      (libsource (lib "eagle-import") (part "IRF3704"))
    )
    (comp (ref "Q9")
      (value "IRF3704")
      (footprint "eagle-import:TO220AH")
      (libsource (lib "eagle-import") (part "IRF3704"))
    )
    (comp (ref "Q10")
      (value "IRF3704")
      (footprint "eagle-import:TO220AH")
      (libsource (lib "eagle-import") (part "IRF3704"))
    )
    (comp (ref "Q11")
      (value "IRF3704")
      (footprint "eagle-import:TO220AH")
      (libsource (lib "eagle-import") (part "IRF3704"))
    )
    (comp (ref "Q12")
      (value "IRF3704")
      (footprint "eagle-import:TO220AH")
      (libsource (lib "eagle-import") (part "IRF3704"))
    )
    (comp (ref "Q13")
      (value "IRF3704")
      (footprint "eagle-import:TO220AH")
      (libsource (lib "eagle-import") (part "IRF3704"))
    )
    (comp (ref "Q14")
      (value "IRF3704")
      (footprint "eagle-import:TO220AH")
      (libsource (lib "eagle-import") (part "IRF3704"))
    )
    (comp (ref "Q15")
      (value "IRF3704")
      (footprint "eagle-import:TO220AH")
      (libsource (lib "eagle-import") (part "IRF3704"))
    )
    (comp (ref "R65")
      (value "22k")
      (footprint "eagle-import:0402-TIGHT")
      (libsource (lib "eagle-import") (part "22KOHM-0402_TIGHT-1/10W-1%"))
    )
    (comp (ref "R66")
      (value "22k")
      (footprint "eagle-import:0402-TIGHT")
      (libsource (lib "eagle-import") (part "22KOHM-0402_TIGHT-1/10W-1%"))
    )
    (comp (ref "R67")
      (value "33k")
      (footprint "eagle-import:0402-TIGHT")
      (libsource (lib "eagle-import") (part "33KOHM-0402T-1/16W-1%"))
    )
    (comp (ref "R68")
      (value "3.3KOHM-0402T-1/16W-1%")
      (footprint "eagle-import:0402-TIGHT")
      (libsource (lib "eagle-import") (part "3.3KOHM-0402T-1/16W-1%"))
    )
    (comp (ref "R69")
      (value "3.3KOHM-0402T-1/16W-1%")
      (footprint "eagle-import:0402-TIGHT")
      (libsource (lib "eagle-import") (part "3.3KOHM-0402T-1/16W-1%"))
    )
    (comp (ref "R70")
      (value "3.3KOHM-0402T-1/16W-1%")
      (footprint "eagle-import:0402-TIGHT")
      (libsource (lib "eagle-import") (part "3.3KOHM-0402T-1/16W-1%"))
    )
    (comp (ref "R71")
      (value "22k")
      (footprint "eagle-import:0402-TIGHT")
      (libsource (lib "eagle-import") (part "22KOHM-0402_TIGHT-1/10W-1%"))
    )
    (comp (ref "R72")
      (value "22k")
      (footprint "eagle-import:0402-TIGHT")
      (libsource (lib "eagle-import") (part "22KOHM-0402_TIGHT-1/10W-1%"))
    )
    (comp (ref "R73")
      (value "33k")
      (footprint "eagle-import:0402-TIGHT")
      (libsource (lib "eagle-import") (part "33KOHM-0402T-1/16W-1%"))
    )
    (comp (ref "R74")
      (value "3.3KOHM-0402T-1/16W-1%")
      (footprint "eagle-import:0402-TIGHT")
      (libsource (lib "eagle-import") (part "3.3KOHM-0402T-1/16W-1%"))
    )
    (comp (ref "R75")
      (value "3.3KOHM-0402T-1/16W-1%")
      (footprint "eagle-import:0402-TIGHT")
      (libsource (lib "eagle-import") (part "3.3KOHM-0402T-1/16W-1%"))
    )
    (comp (ref "R76")
      (value "3.3KOHM-0402T-1/16W-1%")
      (footprint "eagle-import:0402-TIGHT")
      (libsource (lib "eagle-import") (part "3.3KOHM-0402T-1/16W-1%"))
    )
    (comp (ref "R77")
      (value "22k")
      (footprint "eagle-import:0402-TIGHT")
      (libsource (lib "eagle-import") (part "22KOHM-0402_TIGHT-1/10W-1%"))
    )
    (comp (ref "R78")
      (value "22k")
      (footprint "eagle-import:0402-TIGHT")
      (libsource (lib "eagle-import") (part "22KOHM-0402_TIGHT-1/10W-1%"))
    )
    (comp (ref "R79")
      (value "3.3KOHM-0402T-1/16W-1%")
      (footprint "eagle-import:0402-TIGHT")
      (libsource (lib "eagle-import") (part "3.3KOHM-0402T-1/16W-1%"))
    )
    (comp (ref "R80")
      (value "3.3KOHM-0402T-1/16W-1%")
      (footprint "eagle-import:0402-TIGHT")
      (libsource (lib "eagle-import") (part "3.3KOHM-0402T-1/16W-1%"))
    )
    (comp (ref "R81")
      (value "33k")
      (footprint "eagle-import:0402-TIGHT")
      (libsource (lib "eagle-import") (part "33KOHM-0402T-1/16W-1%"))
    )
    (comp (ref "R82")
      (value "3.3KOHM-0402T-1/16W-1%")
      (footprint "eagle-import:0402-TIGHT")
      (libsource (lib "eagle-import") (part "3.3KOHM-0402T-1/16W-1%"))
    )
    (comp (ref "R83")
      (value "22k")
      (footprint "eagle-import:0402-TIGHT")
      (libsource (lib "eagle-import") (part "22KOHM-0402_TIGHT-1/10W-1%"))
    )
    (comp (ref "R84")
      (value "22k")
      (footprint "eagle-import:0402-TIGHT")
      (libsource (lib "eagle-import") (part "22KOHM-0402_TIGHT-1/10W-1%"))
    )
    (comp (ref "R85")
      (value "3.3KOHM-0402T-1/16W-1%")
      (footprint "eagle-import:0402-TIGHT")
      (libsource (lib "eagle-import") (part "3.3KOHM-0402T-1/16W-1%"))
    )
    (comp (ref "R86")
      (value "3.3KOHM-0402T-1/16W-1%")
      (footprint "eagle-import:0402-TIGHT")
      (libsource (lib "eagle-import") (part "3.3KOHM-0402T-1/16W-1%"))
    )
    (comp (ref "VR3")
      (value "10k")
      (footprint "eagle-import:SLIDER-SMALL")
      (libsource (lib "eagle-import") (part "POTENTIOMETER_SLIDE-20MM-1/10W-20%"))
    )
    (comp (ref "C55")
      (value "0.1uF")
      (footprint "eagle-import:0402")
      (libsource (lib "eagle-import") (part "0.1UF-0402-6.3V-10%-X7R"))
    )
    (comp (ref "LED2")
      (value "LEDB152")
      (footprint "eagle-import:Q62902-B152")
      (libsource (lib "eagle-import") (part "LEDB152"))
    )
    (comp (ref "R22")
      (value "100")
      (footprint "eagle-import:0603")
      (libsource (lib "eagle-import") (part "100OHM-0603-1/10W-1%"))
    )
    (comp (ref "R23")
      (value "1KOHM-0402-1/16W-1%")
      (footprint "eagle-import:0402")
      (libsource (lib "eagle-import") (part "1KOHM-0402-1/16W-1%"))
    )
    (comp (ref "R24")
      (value "1KOHM-0402-1/16W-1%")
      (footprint "eagle-import:0402")
      (libsource (lib "eagle-import") (part "1KOHM-0402-1/16W-1%"))
    )
    (comp (ref "R25")
      (value "4.7k")
      (footprint "eagle-import:0402-TIGHT")
      (libsource (lib "eagle-import") (part "4.7KOHM-0402T-1/16W-1%"))
    )
    (comp (ref "R26")
      (value "1KOHM-0402-1/16W-1%")
      (footprint "eagle-import:0402")
      (libsource (lib "eagle-import") (part "1KOHM-0402-1/16W-1%"))
    )
    (comp (ref "R27")
      (value "1KOHM-0402-1/16W-1%")
      (footprint "eagle-import:0402")
      (libsource (lib "eagle-import") (part "1KOHM-0402-1/16W-1%"))
    )
    (comp (ref "R28")
      (value "4.7k")
      (footprint "eagle-import:0402-TIGHT")
      (libsource (lib "eagle-import") (part "4.7KOHM-0402T-1/16W-1%"))
    )
    (comp (ref "R29")
      (value "200OHM-0402T-1/16W-1%")
      (footprint "eagle-import:0402-TIGHT")
      (libsource (lib "eagle-import") (part "200OHM-0402T-1/16W-1%"))
    )
    (comp (ref "R30")
      (value "100")
      (footprint "eagle-import:0603")
      (libsource (lib "eagle-import") (part "100OHM-0603-1/10W-1%"))
    )
    (comp (ref "R31")
      (value "4.7k")
      (footprint "eagle-import:0402-TIGHT")
      (libsource (lib "eagle-import") (part "4.7KOHM-0402T-1/16W-1%"))
    )
    (comp (ref "R32")
      (value "4.7k")
      (footprint "eagle-import:0402-TIGHT")
      (libsource (lib "eagle-import") (part "4.7KOHM-0402T-1/16W-1%"))
    )
    (comp (ref "R33")
      (value "4.7k")
      (footprint "eagle-import:0402-TIGHT")
      (libsource (lib "eagle-import") (part "4.7KOHM-0402T-1/16W-1%"))
    )
    (comp (ref "R34")
      (value "100")
      (footprint "eagle-import:0603")
      (libsource (lib "eagle-import") (part "100OHM-0603-1/10W-1%"))
    )
    (comp (ref "R35")
      (value "1.8k")
      (footprint "eagle-import:0603")
      (libsource (lib "eagle-import") (part "1.8KOHM-0603-1/10W-1%"))
    )
    (comp (ref "R36")
      (value "100")
      (footprint "eagle-import:0603")
      (libsource (lib "eagle-import") (part "100OHM-0603-1/10W-1%"))
    )
    (comp (ref "R37")
      (value "100")
      (footprint "eagle-import:0603")
      (libsource (lib "eagle-import") (part "100OHM-0603-1/10W-1%"))
    )
    (comp (ref "R38")
      (value "1.8k")
      (footprint "eagle-import:0603")
      (libsource (lib "eagle-import") (part "1.8KOHM-0603-1/10W-1%"))
    )
    (comp (ref "R39")
      (value "47")
      (footprint "eagle-import:0603")
      (libsource (lib "eagle-import") (part "47OHM-0603-1/10W-1%"))
    )
    (comp (ref "U1")
      (value "W25Q32FV")
      (footprint "eagle-import:SOIC-8")
      (libsource (lib "eagle-import") (part "W25Q32FVSS"))
    )
    (comp (ref "C2")
      (value "47nf")
      (footprint "eagle-import:C2.5-3")
      (libsource (lib "eagle-import") (part "C2,5-3"))
    )
    (comp (ref "C3")
      (value "47nf")
      (footprint "eagle-import:C2.5-3")
      (libsource (lib "eagle-import") (part "C2,5-3"))
    )
    (comp (ref "C4")
      (value "47nf")
      (footprint "eagle-import:C2.5-3")
      (libsource (lib "eagle-import") (part "C2,5-3"))
    )
    (comp (ref "C5")
      (value "47nf")
      (footprint "eagle-import:C2.5-3")
      (libsource (lib "eagle-import") (part "C2,5-3"))
    )
    (comp (ref "C6")
      (value "47nf")
      (footprint "eagle-import:C2.5-3")
      (libsource (lib "eagle-import") (part "C2,5-3"))
    )
    (comp (ref "C7")
      (value "47nf")
      (footprint "eagle-import:C2.5-3")
      (libsource (lib "eagle-import") (part "C2,5-3"))
    )
    (comp (ref "C8")
      (value "470nf")
      (footprint "eagle-import:C2.5-3")
      (libsource (lib "eagle-import") (part "C2,5-3"))
    )
    (comp (ref "C9")
      (value "47nf")
      (footprint "eagle-import:C2.5-3")
      (libsource (lib "eagle-import") (part "C2,5-3"))
    )
    (comp (ref "C10")
      (value "470nf")
      (footprint "eagle-import:C2.5-3")
      (libsource (lib "eagle-import") (part "C2,5-3"))
    )
    (comp (ref "C11")
      (value "47nf")
      (footprint "eagle-import:C2.5-3")
      (libsource (lib "eagle-import") (part "C2,5-3"))
    )
    (comp (ref "C12")
      (value "47nf")
      (footprint "eagle-import:C2.5-3")
      (libsource (lib "eagle-import") (part "C2,5-3"))
    )
    (comp (ref "C13")
      (value "47nf")
      (footprint "eagle-import:C2.5-3")
      (libsource (lib "eagle-import") (part "C2,5-3"))
    )
    (comp (ref "C14")
      (value "47nf")
      (footprint "eagle-import:C2.5-3")
      (libsource (lib "eagle-import") (part "C2,5-3"))
    )
    (comp (ref "C15")
      (value "47nf")
      (footprint "eagle-import:C2.5-3")
      (libsource (lib "eagle-import") (part "C2,5-3"))
    )
    (comp (ref "C16")
      (value "470nf")
      (footprint "eagle-import:C2.5-3")
      (libsource (lib "eagle-import") (part "C2,5-3"))
    )
    (comp (ref "C17")
      (value "47nf")
      (footprint "eagle-import:C2.5-3")
      (libsource (lib "eagle-import") (part "C2,5-3"))
    )
    (comp (ref "C18")
      (value "10nf")
      (footprint "eagle-import:C2.5-3")
      (libsource (lib "eagle-import") (part "C2,5-3"))
    )
    (comp (ref "C19")
      (value "470nf")
      (footprint "eagle-import:C2.5-3")
      (libsource (lib "eagle-import") (part "C2,5-3"))
    )
    (comp (ref "C20")
      (value "470nf")
      (footprint "eagle-import:C2.5-3")
      (libsource (lib "eagle-import") (part "C2,5-3"))
    )
    (comp (ref "C21")
      (value "470nf")
      (footprint "eagle-import:C2.5-3")
      (libsource (lib "eagle-import") (part "C2,5-3"))
    )
    (comp (ref "C22")
      (value "470nf")
      (footprint "eagle-import:C2.5-3")
      (libsource (lib "eagle-import") (part "C2,5-3"))
    )
    (comp (ref "C23")
      (value "470nf")
      (footprint "eagle-import:C2.5-3")
      (libsource (lib "eagle-import") (part "C2,5-3"))
    )
    (comp (ref "C24")
      (value "4.7uf")
      (footprint "eagle-import:C2.5-3")
      (libsource (lib "eagle-import") (part "C2,5-3"))
    )
    (comp (ref "C25")
      (value "47nf")
      (footprint "eagle-import:C2.5-3")
      (libsource (lib "eagle-import") (part "C2,5-3"))
    )
    (comp (ref "C26")
      (value "470nf")
      (footprint "eagle-import:C2.5-3")
      (libsource (lib "eagle-import") (part "C2,5-3"))
    )
    (comp (ref "C27")
      (value "470nf")
      (footprint "eagle-import:C2.5-3")
      (libsource (lib "eagle-import") (part "C2,5-3"))
    )
    (comp (ref "C28")
      (value "470nf")
      (footprint "eagle-import:C2.5-3")
      (libsource (lib "eagle-import") (part "C2,5-3"))
    )
    (comp (ref "C29")
      (value "470nf")
      (footprint "eagle-import:C2.5-3")
      (libsource (lib "eagle-import") (part "C2,5-3"))
    )
    (comp (ref "C30")
      (value "47uf")
      (footprint "eagle-import:C2.5-3")
      (libsource (lib "eagle-import") (part "C2,5-3"))
    )
    (comp (ref "C31")
      (value "470nf")
      (footprint "eagle-import:C2.5-3")
      (libsource (lib "eagle-import") (part "C2,5-3"))
    )
    (comp (ref "C32")
      (value "4.7uf")
      (footprint "eagle-import:C2.5-3")
      (libsource (lib "eagle-import") (part "C2,5-3"))
    )
    (comp (ref "C33")
      (value "470nf")
      (footprint "eagle-import:C2.5-3")
      (libsource (lib "eagle-import") (part "C2,5-3"))
    )
    (comp (ref "C34")
      (value "470nf")
      (footprint "eagle-import:C2.5-3")
      (libsource (lib "eagle-import") (part "C2,5-3"))
    )
    (comp (ref "C35")
      (value "470nf")
      (footprint "eagle-import:C2.5-3")
      (libsource (lib "eagle-import") (part "C2,5-3"))
    )
    (comp (ref "C36")
      (value "470nf")
      (footprint "eagle-import:C2.5-3")
      (libsource (lib "eagle-import") (part "C2,5-3"))
    )
    (comp (ref "C37")
      (value "4.7uf")
      (footprint "eagle-import:C2.5-3")
      (libsource (lib "eagle-import") (part "C2,5-3"))
    )
    (comp (ref "C38")
      (value "4.7uf")
      (footprint "eagle-import:C2.5-3")
      (libsource (lib "eagle-import") (part "C2,5-3"))
    )
    (comp (ref "C39")
      (value "100uf")
      (footprint "eagle-import:C2.5-3")
      (libsource (lib "eagle-import") (part "C2,5-3"))
    )
    (comp (ref "C40")
      (value "470nf")
      (footprint "eagle-import:C2.5-3")
      (libsource (lib "eagle-import") (part "C2,5-3"))
    )
    (comp (ref "C41")
      (value "470nf")
      (footprint "eagle-import:C2.5-3")
      (libsource (lib "eagle-import") (part "C2,5-3"))
    )
    (comp (ref "C42")
      (value "470nf")
      (footprint "eagle-import:C2.5-3")
      (libsource (lib "eagle-import") (part "C2,5-3"))
    )
    (comp (ref "C43")
      (value "47uf")
      (footprint "eagle-import:C2.5-3")
      (libsource (lib "eagle-import") (part "C2,5-3"))
    )
    (comp (ref "C44")
      (value "4.7uf")
      (footprint "eagle-import:C2.5-3")
      (libsource (lib "eagle-import") (part "C2,5-3"))
    )
    (comp (ref "C45")
      (value "4.7uf")
      (footprint "eagle-import:C2.5-3")
      (libsource (lib "eagle-import") (part "C2,5-3"))
    )
    (comp (ref "C46")
      (value "4.7uf")
      (footprint "eagle-import:C2.5-3")
      (libsource (lib "eagle-import") (part "C2,5-3"))
    )
    (comp (ref "C47")
      (value "4.7uf")
      (footprint "eagle-import:C2.5-3")
      (libsource (lib "eagle-import") (part "C2,5-3"))
    )
    (comp (ref "C48")
      (value "100uf")
      (footprint "eagle-import:C2.5-3")
      (libsource (lib "eagle-import") (part "C2,5-3"))
    )
    (comp (ref "L1")
      (value "P0762.154NL")
      (footprint "eagle-import:P0762NL")
      (libsource (lib "eagle-import") (part "P0762.NL154"))
    )
    (comp (ref "L2")
      (value "P0762.154NL")
      (footprint "eagle-import:P0762NL")
      (libsource (lib "eagle-import") (part "P0762.NL154"))
    )
    (comp (ref "R1")
      (value "0")
      (footprint "eagle-import:0402")
      (libsource (lib "eagle-import") (part "0OHM-0402-1/10W"))
    )
  )
  (nets
    (net (code "1") (name "A2") (class "Default")
      (node (ref "IC1") (pin "A2") (pinfunction "IO_L2N_T0_34_A2") (pintype "bidirectional"))
      (node (ref "IC4") (pin "6") (pinfunction "SCLK_6") (pintype "bidirectional"))
    )
    (net (code "2") (name "A3") (class "Default")
      (node (ref "IC1") (pin "A3") (pinfunction "IO_L1N_T0_34_A3") (pintype "bidirectional"))
      (node (ref "IC4") (pin "5") (pinfunction "~{SYNC}_5") (pintype "bidirectional"))
      (node (ref "R63") (pin "2") (pinfunction "2_2") (pintype "passive"))
    )
    (net (code "3") (name "A11") (class "Default")
      (node (ref "C57") (pin "1") (pinfunction "1_1") (pintype "passive"))
      (node (ref "IC1") (pin "A11") (pinfunction "IO_L11P_T1_SRCC_AD12P_15_A11") (pintype "bidirectional"))
      (node (ref "R42") (pin "1") (pinfunction "1_1") (pintype "passive"))
    )
    (net (code "4") (name "A12") (class "Default")
      (node (ref "C57") (pin "2") (pinfunction "2_2") (pintype "passive"))
      (node (ref "IC1") (pin "A12") (pinfunction "IO_L11N_T1_SRCC_AD12N_15_A12") (pintype "bidirectional"))
      (node (ref "R43") (pin "1") (pinfunction "1_1") (pintype "passive"))
    )
    (net (code "5") (name "A13") (class "Default")
      (node (ref "C56") (pin "1") (pinfunction "1_1") (pintype "passive"))
      (node (ref "IC1") (pin "A13") (pinfunction "IO_L12P_T1_MRCC_AD5P_15_A13") (pintype "bidirectional"))
      (node (ref "R40") (pin "1") (pinfunction "1_1") (pintype "passive"))
    )
    (net (code "6") (name "A14") (class "Default")
      (node (ref "C56") (pin "2") (pinfunction "2_2") (pintype "passive"))
      (node (ref "IC1") (pin "A14") (pinfunction "IO_L12N_T1_MRCC_AD5N_15_A14") (pintype "bidirectional"))
      (node (ref "R41") (pin "1") (pinfunction "1_1") (pintype "passive"))
    )
    (net (code "7") (name "B1") (class "Default")
      (node (ref "IC1") (pin "B1") (pinfunction "IO_L4N_T0_34_B1") (pintype "bidirectional"))
      (node (ref "Q5") (pin "E") (pinfunction "S_E") (pintype "passive"))
      (node (ref "R65") (pin "1") (pinfunction "1_1") (pintype "passive"))
    )
    (net (code "8") (name "B2") (class "Default")
      (node (ref "IC1") (pin "B2") (pinfunction "IO_L2P_T0_34_B2") (pintype "bidirectional"))
      (node (ref "IC4") (pin "7") (pinfunction "DIN_7") (pintype "bidirectional"))
    )
    (net (code "9") (name "B10") (class "Default")
      (node (ref "IC1") (pin "B10") (pinfunction "IO_L8N_T1_AD3N_15_B10") (pintype "bidirectional"))
      (node (ref "Q13") (pin "B") (pinfunction "G_B") (pintype "passive"))
      (node (ref "R81") (pin "1") (pinfunction "1_1") (pintype "passive"))
    )
    (net (code "10") (name "B11") (class "Default")
      (node (ref "IC1") (pin "B11") (pinfunction "IO_L10P_T1_AD4P_15_B11") (pintype "bidirectional"))
      (node (ref "Q11") (pin "E") (pinfunction "S_E") (pintype "passive"))
      (node (ref "R77") (pin "1") (pinfunction "1_1") (pintype "passive"))
    )
    (net (code "11") (name "B12") (class "Default")
      (node (ref "IC1") (pin "B12") (pinfunction "IO_L10N_T1_AD4N_15_B12") (pintype "bidirectional"))
      (node (ref "Q8") (pin "E") (pinfunction "S_E") (pintype "passive"))
      (node (ref "R71") (pin "1") (pinfunction "1_1") (pintype "passive"))
    )
    (net (code "12") (name "C5") (class "Default")
      (node (ref "IC1") (pin "C5") (pinfunction "IO_L5P_T0_34_C5") (pintype "bidirectional"))
      (node (ref "Q14") (pin "E") (pinfunction "S_E") (pintype "passive"))
      (node (ref "R83") (pin "1") (pinfunction "1_1") (pintype "passive"))
    )
    (net (code "13") (name "C6") (class "Default")
      (node (ref "IC1") (pin "C6") (pinfunction "IO_L1P_T0_AD0P_15_C6") (pintype "bidirectional"))
      (node (ref "Q6") (pin "E") (pinfunction "S_E") (pintype "passive"))
      (node (ref "R66") (pin "1") (pinfunction "1_1") (pintype "passive"))
    )
    (net (code "14") (name "C7") (class "Default")
      (node (ref "IC1") (pin "C7") (pinfunction "IO_L1N_T0_AD0N_15_C7") (pintype "bidirectional"))
      (node (ref "Q9") (pin "E") (pinfunction "S_E") (pintype "passive"))
      (node (ref "R72") (pin "1") (pinfunction "1_1") (pintype "passive"))
    )
    (net (code "15") (name "C8") (class "Default")
      (node (ref "IC1") (pin "C8") (pinfunction "IO_L4P_T0_AD9P_15_C8") (pintype "bidirectional"))
      (node (ref "Q12") (pin "E") (pinfunction "S_E") (pintype "passive"))
      (node (ref "R78") (pin "1") (pinfunction "1_1") (pintype "passive"))
    )
    (net (code "16") (name "D1") (class "Default")
      (node (ref "IC1") (pin "D1") (pinfunction "IO_L6N_T0_VREF_34_D1") (pintype "bidirectional"))
      (node (ref "R59") (pin "2") (pinfunction "2_2") (pintype "passive"))
    )
    (net (code "17") (name "D2") (class "Default")
      (node (ref "IC1") (pin "D2") (pinfunction "IO_L6P_T0_34_D2") (pintype "bidirectional"))
      (node (ref "R58") (pin "2") (pinfunction "2_2") (pintype "passive"))
    )
    (net (code "18") (name "DAC_O1") (class "Default")
      (node (ref "IC4") (pin "4") (pinfunction "VOUTA_4") (pintype "bidirectional"))
      (node (ref "R62") (pin "1") (pinfunction "1_1") (pintype "passive"))
    )
    (net (code "19") (name "DAC_O2") (class "Default")
      (node (ref "IC4") (pin "3") (pinfunction "VOUTB_3") (pintype "bidirectional"))
      (node (ref "R64") (pin "2") (pinfunction "2_2") (pintype "passive"))
    )
    (net (code "20") (name "DL0") (class "Default")
      (node (ref "DIS1") (pin "7") (pinfunction "D0_7") (pintype "input"))
      (node (ref "Q5") (pin "C") (pinfunction "D_C") (pintype "passive"))
      (node (ref "R68") (pin "1") (pinfunction "1_1") (pintype "passive"))
    )
    (net (code "21") (name "DL1") (class "Default")
      (node (ref "DIS1") (pin "8") (pinfunction "D1_8") (pintype "input"))
      (node (ref "Q8") (pin "C") (pinfunction "D_C") (pintype "passive"))
      (node (ref "R74") (pin "1") (pinfunction "1_1") (pintype "passive"))
    )
    (net (code "22") (name "DL2") (class "Default")
      (node (ref "DIS1") (pin "9") (pinfunction "D2_9") (pintype "input"))
      (node (ref "Q11") (pin "C") (pinfunction "D_C") (pintype "passive"))
      (node (ref "R79") (pin "1") (pinfunction "1_1") (pintype "passive"))
    )
    (net (code "23") (name "DL3") (class "Default")
      (node (ref "DIS1") (pin "10") (pinfunction "D3_10") (pintype "input"))
      (node (ref "Q14") (pin "C") (pinfunction "D_C") (pintype "passive"))
      (node (ref "R85") (pin "1") (pinfunction "1_1") (pintype "passive"))
    )
    (net (code "24") (name "DL4") (class "Default")
      (node (ref "DIS1") (pin "11") (pinfunction "D4_11") (pintype "input"))
      (node (ref "Q6") (pin "C") (pinfunction "D_C") (pintype "passive"))
      (node (ref "R69") (pin "1") (pinfunction "1_1") (pintype "passive"))
    )
    (net (code "25") (name "DL5") (class "Default")
      (node (ref "DIS1") (pin "12") (pinfunction "D5_12") (pintype "input"))
      (node (ref "Q9") (pin "C") (pinfunction "D_C") (pintype "passive"))
      (node (ref "R75") (pin "1") (pinfunction "1_1") (pintype "passive"))
    )
    (net (code "26") (name "DL6") (class "Default")
      (node (ref "DIS1") (pin "13") (pinfunction "D6_13") (pintype "input"))
      (node (ref "Q12") (pin "C") (pinfunction "D_C") (pintype "passive"))
      (node (ref "R80") (pin "1") (pinfunction "1_1") (pintype "passive"))
    )
    (net (code "27") (name "DL7") (class "Default")
      (node (ref "DIS1") (pin "14") (pinfunction "D7_14") (pintype "input"))
      (node (ref "Q15") (pin "C") (pinfunction "D_C") (pintype "passive"))
      (node (ref "R86") (pin "1") (pinfunction "1_1") (pintype "passive"))
    )
    (net (code "28") (name "E") (class "Default")
      (node (ref "DIS1") (pin "6") (pinfunction "E_6") (pintype "input"))
      (node (ref "Q13") (pin "C") (pinfunction "D_C") (pintype "passive"))
      (node (ref "R82") (pin "1") (pinfunction "1_1") (pintype "passive"))
    )
    (net (code "29") (name "E1") (class "Default")
      (node (ref "IC1") (pin "E1") (pinfunction "IO_L8N_T1_34_E1") (pintype "bidirectional"))
      (node (ref "R57") (pin "1") (pinfunction "1_1") (pintype "passive"))
    )
    (net (code "30") (name "E2") (class "Default")
      (node (ref "IC1") (pin "E2") (pinfunction "IO_L8P_T1_34_E2") (pintype "bidirectional"))
      (node (ref "R54") (pin "1") (pinfunction "1_1") (pintype "passive"))
    )
    (net (code "31") (name "E11") (class "Default")
      (node (ref "IC1") (pin "E11") (pinfunction "IO_L17N_T2_15_E11") (pintype "bidirectional"))
      (node (ref "Q15") (pin "E") (pinfunction "S_E") (pintype "passive"))
      (node (ref "R84") (pin "1") (pinfunction "1_1") (pintype "passive"))
    )
    (net (code "32") (name "E12") (class "Default")
      (node (ref "IC1") (pin "E12") (pinfunction "IO_L18P_T2_15_E12") (pintype "bidirectional"))
      (node (ref "Q7") (pin "B") (pinfunction "G_B") (pintype "passive"))
      (node (ref "R67") (pin "1") (pinfunction "1_1") (pintype "passive"))
    )
    (net (code "33") (name "E13") (class "Default")
      (node (ref "IC1") (pin "E13") (pinfunction "IO_L18N_T2_15_E13") (pintype "bidirectional"))
      (node (ref "Q10") (pin "B") (pinfunction "G_B") (pintype "passive"))
      (node (ref "R73") (pin "1") (pinfunction "1_1") (pintype "passive"))
    )
    (net (code "34") (name "EN3") (class "Default")
      (node (ref "IC2") (pin "12") (pinfunction "EN3_12") (pintype "bidirectional"))
      (node (ref "R2") (pin "1") (pinfunction "1_1") (pintype "passive"))
      (node (ref "R3") (pin "2") (pinfunction "2_2") (pintype "passive"))
    )
    (net (code "35") (name "F5") (class "Default")
      (node (ref "IC1") (pin "F5") (pinfunction "CCLK_0_F5") (pintype "bidirectional"))
      (node (ref "R39") (pin "1") (pinfunction "1_1") (pintype "passive"))
      (node (ref "U1") (pin "6") (pinfunction "SCK_6") (pintype "bidirectional"))
    )
    (net (code "36") (name "G5") (class "Default")
      (node (ref "IC1") (pin "G5") (pinfunction "DONE_0_G5") (pintype "bidirectional"))
      (node (ref "R29") (pin "1") (pinfunction "1_1") (pintype "passive"))
      (node (ref "R30") (pin "2") (pinfunction "2_2") (pintype "passive"))
    )
    (net (code "37") (name "GND") (class "Default")
      (node (ref "C1") (pin "2") (pinfunction "2_2") (pintype "passive"))
      (node (ref "C10") (pin "2") (pinfunction "2_2") (pintype "passive"))
      (node (ref "C11") (pin "2") (pinfunction "2_2") (pintype "passive"))
      (node (ref "C12") (pin "2") (pinfunction "2_2") (pintype "passive"))
      (node (ref "C13") (pin "2") (pinfunction "2_2") (pintype "passive"))
      (node (ref "C14") (pin "2") (pinfunction "2_2") (pintype "passive"))
      (node (ref "C15") (pin "2") (pinfunction "2_2") (pintype "passive"))
      (node (ref "C16") (pin "2") (pinfunction "2_2") (pintype "passive"))
      (node (ref "C17") (pin "2") (pinfunction "2_2") (pintype "passive"))
      (node (ref "C19") (pin "2") (pinfunction "2_2") (pintype "passive"))
      (node (ref "C2") (pin "2") (pinfunction "2_2") (pintype "passive"))
      (node (ref "C20") (pin "2") (pinfunction "2_2") (pintype "passive"))
      (node (ref "C21") (pin "2") (pinfunction "2_2") (pintype "passive"))
      (node (ref "C22") (pin "2") (pinfunction "2_2") (pintype "passive"))
      (node (ref "C23") (pin "2") (pinfunction "2_2") (pintype "passive"))
      (node (ref "C24") (pin "2") (pinfunction "2_2") (pintype "passive"))
      (node (ref "C25") (pin "2") (pinfunction "2_2") (pintype "passive"))
      (node (ref "C26") (pin "2") (pinfunction "2_2") (pintype "passive"))
      (node (ref "C27") (pin "2") (pinfunction "2_2") (pintype "passive"))
      (node (ref "C28") (pin "2") (pinfunction "2_2") (pintype "passive"))
      (node (ref "C29") (pin "2") (pinfunction "2_2") (pintype "passive"))
      (node (ref "C3") (pin "2") (pinfunction "2_2") (pintype "passive"))
      (node (ref "C30") (pin "2") (pinfunction "2_2") (pintype "passive"))
      (node (ref "C31") (pin "2") (pinfunction "2_2") (pintype "passive"))
      (node (ref "C32") (pin "2") (pinfunction "2_2") (pintype "passive"))
      (node (ref "C33") (pin "2") (pinfunction "2_2") (pintype "passive"))
      (node (ref "C34") (pin "2") (pinfunction "2_2") (pintype "passive"))
      (node (ref "C35") (pin "2") (pinfunction "2_2") (pintype "passive"))
      (node (ref "C36") (pin "2") (pinfunction "2_2") (pintype "passive"))
      (node (ref "C37") (pin "2") (pinfunction "2_2") (pintype "passive"))
      (node (ref "C38") (pin "2") (pinfunction "2_2") (pintype "passive"))
      (node (ref "C39") (pin "2") (pinfunction "2_2") (pintype "passive"))
      (node (ref "C4") (pin "2") (pinfunction "2_2") (pintype "passive"))
      (node (ref "C40") (pin "2") (pinfunction "2_2") (pintype "passive"))
      (node (ref "C41") (pin "2") (pinfunction "2_2") (pintype "passive"))
      (node (ref "C42") (pin "2") (pinfunction "2_2") (pintype "passive"))
      (node (ref "C43") (pin "2") (pinfunction "2_2") (pintype "passive"))
      (node (ref "C44") (pin "2") (pinfunction "2_2") (pintype "passive"))
      (node (ref "C45") (pin "2") (pinfunction "2_2") (pintype "passive"))
      (node (ref "C46") (pin "2") (pinfunction "2_2") (pintype "passive"))
      (node (ref "C47") (pin "2") (pinfunction "2_2") (pintype "passive"))
      (node (ref "C48") (pin "2") (pinfunction "2_2") (pintype "passive"))
      (node (ref "C49") (pin "2") (pinfunction "2_2") (pintype "passive"))
      (node (ref "C5") (pin "2") (pinfunction "2_2") (pintype "passive"))
      (node (ref "C50") (pin "2") (pinfunction "2_2") (pintype "passive"))
      (node (ref "C52") (pin "2") (pinfunction "2_2") (pintype "passive"))
      (node (ref "C53") (pin "2") (pinfunction "2_2") (pintype "passive"))
      (node (ref "C54") (pin "2") (pinfunction "2_2") (pintype "passive"))
      (node (ref "C55") (pin "2") (pinfunction "2_2") (pintype "passive"))
      (node (ref "C58") (pin "2") (pinfunction "2_2") (pintype "passive"))
      (node (ref "C59") (pin "2") (pinfunction "2_2") (pintype "passive"))
      (node (ref "C6") (pin "2") (pinfunction "2_2") (pintype "passive"))
      (node (ref "C60") (pin "2") (pinfunction "2_2") (pintype "passive"))
      (node (ref "C62") (pin "2") (pinfunction "2_2") (pintype "passive"))
      (node (ref "C63") (pin "2") (pinfunction "2_2") (pintype "passive"))
      (node (ref "C64") (pin "2") (pinfunction "2_2") (pintype "passive"))
      (node (ref "C65") (pin "2") (pinfunction "2_2") (pintype "passive"))
      (node (ref "C67") (pin "2") (pinfunction "2_2") (pintype "passive"))
      (node (ref "C68") (pin "2") (pinfunction "2_2") (pintype "passive"))
      (node (ref "C69") (pin "2") (pinfunction "2_2") (pintype "passive"))
      (node (ref "C7") (pin "2") (pinfunction "2_2") (pintype "passive"))
      (node (ref "C70") (pin "2") (pinfunction "2_2") (pintype "passive"))
      (node (ref "C71") (pin "2") (pinfunction "2_2") (pintype "passive"))
      (node (ref "C8") (pin "2") (pinfunction "2_2") (pintype "passive"))
      (node (ref "C9") (pin "2") (pinfunction "2_2") (pintype "passive"))
      (node (ref "D1") (pin "A") (pinfunction "A_A") (pintype "passive"))
      (node (ref "DIS1") (pin "1") (pinfunction "GND_1") (pintype "power_in"))
      (node (ref "GS1") (pin "HA") (pinfunction "H1_HA") (pintype "bidirectional"))
      (node (ref "IC1") (pin "A1") (pinfunction "GND_1_A1") (pintype "bidirectional"))
      (node (ref "IC1") (pin "A15") (pinfunction "GND_2_A15") (pintype "bidirectional"))
      (node (ref "IC1") (pin "B8") (pinfunction "GND_3_B8") (pintype "bidirectional"))
      (node (ref "IC1") (pin "C12") (pinfunction "GND_5_C12") (pintype "bidirectional"))
      (node (ref "IC1") (pin "C2") (pinfunction "GND_4_C2") (pintype "bidirectional"))
      (node (ref "IC1") (pin "D14") (pinfunction "GND_7_D14") (pintype "bidirectional"))
      (node (ref "IC1") (pin "D6") (pinfunction "GND_6_D6") (pintype "bidirectional"))
      (node (ref "IC1") (pin "E4") (pinfunction "GND_8_E4") (pintype "bidirectional"))
      (node (ref "IC1") (pin "E7") (pinfunction "GND_9_E7") (pintype "bidirectional"))
      (node (ref "IC1") (pin "E9") (pinfunction "GND_10_E9") (pintype "bidirectional"))
      (node (ref "IC1") (pin "F10") (pinfunction "GND_12_F10") (pintype "bidirectional"))
      (node (ref "IC1") (pin "F13") (pinfunction "GND_13_F13") (pintype "bidirectional"))
      (node (ref "IC1") (pin "F6") (pinfunction "GND_11_F6") (pintype "bidirectional"))
      (node (ref "IC1") (pin "G3") (pinfunction "GND_14_G3") (pintype "bidirectional"))
      (node (ref "IC1") (pin "G7") (pinfunction "GND_15_G7") (pintype "bidirectional"))
      (node (ref "IC1") (pin "H10") (pinfunction "GND_17_H10") (pintype "bidirectional"))
      (node (ref "IC1") (pin "H6") (pinfunction "GND_16_H6") (pintype "bidirectional"))
      (node (ref "IC1") (pin "J13") (pinfunction "GND_19_J13") (pintype "bidirectional"))
      (node (ref "IC1") (pin "J7") (pinfunction "GND_18_J7") (pintype "bidirectional"))
      (node (ref "IC1") (pin "J8") (pinfunction "DXN_0_J8") (pintype "bidirectional"))
      (node (ref "IC1") (pin "J9") (pinfunction "DXP_0_J9") (pintype "bidirectional"))
      (node (ref "IC1") (pin "K10") (pinfunction "GND_22_K10") (pintype "bidirectional"))
      (node (ref "IC1") (pin "K6") (pinfunction "GND_20_K6") (pintype "bidirectional"))
      (node (ref "IC1") (pin "K8") (pinfunction "GND_21_K8") (pintype "bidirectional"))
      (node (ref "IC1") (pin "L2") (pinfunction "GND_23_L2") (pintype "bidirectional"))
      (node (ref "IC1") (pin "L7") (pinfunction "GND_24_L7") (pintype "bidirectional"))
      (node (ref "IC1") (pin "L9") (pinfunction "GND_25_L9") (pintype "bidirectional"))
      (node (ref "IC1") (pin "M11") (pinfunction "GND_26_M11") (pintype "bidirectional"))
      (node (ref "IC1") (pin "P13") (pinfunction "GND_29_P13") (pintype "bidirectional"))
      (node (ref "IC1") (pin "P4") (pinfunction "GND_27_P4") (pintype "bidirectional"))
      (node (ref "IC1") (pin "P8") (pinfunction "GND_28_P8") (pintype "bidirectional"))
      (node (ref "IC1") (pin "R1") (pinfunction "GND_30_R1") (pintype "bidirectional"))
      (node (ref "IC1") (pin "R15") (pinfunction "GND_31_R15") (pintype "bidirectional"))
      (node (ref "IC2") (pin "1") (pinfunction "PGND2_1") (pintype "bidirectional"))
      (node (ref "IC2") (pin "11") (pinfunction "SGND_11") (pintype "bidirectional"))
      (node (ref "IC2") (pin "15") (pinfunction "PGND3_15") (pintype "bidirectional"))
      (node (ref "IC2") (pin "20") (pinfunction "PGND1_20") (pintype "bidirectional"))
      (node (ref "IC2") (pin "21") (pinfunction "GND_21") (pintype "bidirectional"))
      (node (ref "IC2") (pin "7") (pinfunction "FB2_7") (pintype "bidirectional"))
      (node (ref "IC2") (pin "8") (pinfunction "FB1_8") (pintype "bidirectional"))
      (node (ref "IC2") (pin "9") (pinfunction "FB3_9") (pintype "bidirectional"))
      (node (ref "IC3") (pin "4") (pinfunction "V-_4") (pintype "bidirectional"))
      (node (ref "IC4") (pin "8") (pinfunction "GND_8") (pintype "bidirectional"))
      (node (ref "JP1") (pin "1") (pinfunction "1_1") (pintype "passive"))
      (node (ref "JP1") (pin "11") (pinfunction "11_11") (pintype "passive"))
      (node (ref "JP1") (pin "13") (pinfunction "13_13") (pintype "passive"))
      (node (ref "JP1") (pin "3") (pinfunction "3_3") (pintype "passive"))
      (node (ref "JP1") (pin "5") (pinfunction "5_5") (pintype "passive"))
      (node (ref "JP1") (pin "7") (pinfunction "7_7") (pintype "passive"))
      (node (ref "JP1") (pin "9") (pinfunction "9_9") (pintype "passive"))
      (node (ref "L1") (pin "1") (pinfunction "1_1") (pintype "passive"))
      (node (ref "LED2") (pin "K") (pinfunction "C_K") (pintype "passive"))
      (node (ref "LED3") (pin "K") (pinfunction "C_K") (pintype "passive"))
      (node (ref "LED4") (pin "K") (pinfunction "C_K") (pintype "passive"))
      (node (ref "LED5") (pin "K") (pinfunction "C_K") (pintype "passive"))
      (node (ref "LED6") (pin "K") (pinfunction "C_K") (pintype "passive"))
      (node (ref "LS1") (pin "-") (pinfunction "2_-") (pintype "passive"))
      (node (ref "LS2") (pin "-") (pinfunction "2_-") (pintype "passive"))
      (node (ref "Q10") (pin "E") (pinfunction "S_E") (pintype "passive"))
      (node (ref "Q13") (pin "E") (pinfunction "S_E") (pintype "passive"))
      (node (ref "Q2") (pin "3") (pinfunction "E_3") (pintype "passive"))
      (node (ref "Q3") (pin "3") (pinfunction "E_3") (pintype "passive"))
      (node (ref "Q4") (pin "3") (pinfunction "S_3") (pintype "passive"))
      (node (ref "Q7") (pin "E") (pinfunction "S_E") (pintype "passive"))
      (node (ref "R12") (pin "1") (pinfunction "1_1") (pintype "passive"))
      (node (ref "R16") (pin "2") (pinfunction "2_2") (pintype "passive"))
      (node (ref "R18") (pin "2") (pinfunction "2_2") (pintype "passive"))
      (node (ref "R19") (pin "1") (pinfunction "1_1") (pintype "passive"))
      (node (ref "R19") (pin "2") (pinfunction "2_2") (pintype "passive"))
      (node (ref "R24") (pin "2") (pinfunction "2_2") (pintype "passive"))
      (node (ref "R27") (pin "2") (pinfunction "2_2") (pintype "passive"))
      (node (ref "R3") (pin "1") (pinfunction "1_1") (pintype "passive"))
      (node (ref "R41") (pin "2") (pinfunction "2_2") (pintype "passive"))
      (node (ref "R43") (pin "2") (pinfunction "2_2") (pintype "passive"))
      (node (ref "R44") (pin "1") (pinfunction "1_1") (pintype "passive"))
      (node (ref "R45") (pin "1") (pinfunction "1_1") (pintype "passive"))
      (node (ref "R5") (pin "1") (pinfunction "1_1") (pintype "passive"))
      (node (ref "R5") (pin "2") (pinfunction "2_2") (pintype "passive"))
      (node (ref "R50") (pin "1") (pinfunction "1_1") (pintype "passive"))
      (node (ref "R51") (pin "1") (pinfunction "1_1") (pintype "passive"))
      (node (ref "R52") (pin "1") (pinfunction "1_1") (pintype "passive"))
      (node (ref "R53") (pin "1") (pinfunction "1_1") (pintype "passive"))
      (node (ref "R6") (pin "1") (pinfunction "1_1") (pintype "passive"))
      (node (ref "R9") (pin "1") (pinfunction "1_1") (pintype "passive"))
      (node (ref "U1") (pin "4") (pinfunction "GND_4") (pintype "bidirectional"))
      (node (ref "U2") (pin "1") (pinfunction "GND_1") (pintype "power_in"))
      (node (ref "VR1") (pin "1") (pinfunction "CCW_1") (pintype "passive"))
      (node (ref "VR2") (pin "BOTTOM") (pinfunction "A_BOTTOM") (pintype "passive"))
      (node (ref "VR3") (pin "BOTTOM") (pinfunction "A_BOTTOM") (pintype "passive"))
      (node (ref "Y1") (pin "2") (pinfunction "GND_2") (pintype "bidirectional"))
    )
    (net (code "38") (name "H5") (class "Default")
      (node (ref "IC1") (pin "H5") (pinfunction "CFGBVS_0_H5") (pintype "bidirectional"))
      (node (ref "R28") (pin "1") (pinfunction "1_1") (pintype "passive"))
    )
    (net (code "39") (name "H14") (class "Default")
      (node (ref "IC1") (pin "H14") (pinfunction "IO_L1P_T0_D00_MOSI_14_H14") (pintype "bidirectional"))
      (node (ref "R37") (pin "2") (pinfunction "2_2") (pintype "passive"))
    )
    (net (code "40") (name "H15") (class "Default")
      (node (ref "IC1") (pin "H15") (pinfunction "IO_L1N_T0_D01_DIN_14_H15") (pintype "bidirectional"))
      (node (ref "R22") (pin "1") (pinfunction "1_1") (pintype "passive"))
    )
    (net (code "41") (name "HOLD") (class "Default")
      (node (ref "R34") (pin "2") (pinfunction "2_2") (pintype "passive"))
      (node (ref "R35") (pin "1") (pinfunction "1_1") (pintype "passive"))
      (node (ref "U1") (pin "7") (pinfunction "~{HOLD}(D3)_7") (pintype "bidirectional"))
    )
    (net (code "42") (name "J1") (class "Default")
      (node (ref "IC1") (pin "J1") (pinfunction "IO_L16N_T2_34_J1") (pintype "bidirectional"))
      (node (ref "R56") (pin "1") (pinfunction "1_1") (pintype "passive"))
    )
    (net (code "43") (name "J5") (class "Default")
      (node (ref "IC1") (pin "J5") (pinfunction "PROGRAM_B_0_J5") (pintype "bidirectional"))
      (node (ref "R31") (pin "1") (pinfunction "1_1") (pintype "passive"))
    )
    (net (code "44") (name "J12") (class "Default")
      (node (ref "IC1") (pin "J12") (pinfunction "IO_L2P_T0_D02_14_J12") (pintype "bidirectional"))
      (node (ref "R36") (pin "1") (pinfunction "1_1") (pintype "passive"))
    )
    (net (code "45") (name "K1") (class "Default")
      (node (ref "IC1") (pin "K1") (pinfunction "IO_L16P_T2_34_K1") (pintype "bidirectional"))
      (node (ref "R55") (pin "1") (pinfunction "1_1") (pintype "passive"))
    )
    (net (code "46") (name "K2") (class "Default")
      (node (ref "IC1") (pin "K2") (pinfunction "IO_L17N_T2_34_K2") (pintype "bidirectional"))
      (node (ref "R61") (pin "2") (pinfunction "2_2") (pintype "passive"))
    )
    (net (code "47") (name "K3") (class "Default")
      (node (ref "IC1") (pin "K3") (pinfunction "IO_L17P_T2_34_K3") (pintype "bidirectional"))
      (node (ref "R60") (pin "2") (pinfunction "2_2") (pintype "passive"))
    )
    (net (code "48") (name "K11") (class "Default")
      (node (ref "IC1") (pin "K11") (pinfunction "IO_L3P_T0_DQS_PUDC_B_14_K11") (pintype "bidirectional"))
      (node (ref "R23") (pin "1") (pinfunction "1_1") (pintype "passive"))
    )
    (net (code "49") (name "K12") (class "Default")
      (node (ref "IC1") (pin "K12") (pinfunction "IO_L3N_T0_DQS_EMCCLK_14_K12") (pintype "bidirectional"))
      (node (ref "R39") (pin "2") (pinfunction "2_2") (pintype "passive"))
    )
    (net (code "50") (name "K13") (class "Default")
      (node (ref "IC1") (pin "K13") (pinfunction "IO_L2N_T0_D03_14_K13") (pintype "bidirectional"))
      (node (ref "R34") (pin "1") (pinfunction "1_1") (pintype "passive"))
    )
    (net (code "51") (name "L5") (class "Default")
      (node (ref "IC1") (pin "L5") (pinfunction "INIT_B_0_L5") (pintype "bidirectional"))
      (node (ref "R32") (pin "1") (pinfunction "1_1") (pintype "passive"))
    )
    (net (code "52") (name "L11") (class "Default")
      (node (ref "IC1") (pin "L11") (pinfunction "IO_L6P_T0_FCS_B_14_L11") (pintype "bidirectional"))
      (node (ref "R25") (pin "1") (pinfunction "1_1") (pintype "passive"))
      (node (ref "R33") (pin "1") (pinfunction "1_1") (pintype "passive"))
      (node (ref "U1") (pin "1") (pinfunction "~{CS}_1") (pintype "bidirectional"))
    )
    (net (code "53") (name "M5") (class "Default")
      (node (ref "IC1") (pin "M5") (pinfunction "M0_0_M5") (pintype "bidirectional"))
      (node (ref "R26") (pin "1") (pinfunction "1_1") (pintype "passive"))
    )
    (net (code "54") (name "M6") (class "Default")
      (node (ref "IC1") (pin "M6") (pinfunction "M2_0_M6") (pintype "bidirectional"))
      (node (ref "R27") (pin "1") (pinfunction "1_1") (pintype "passive"))
    )
    (net (code "55") (name "M9") (class "Default")
      (node (ref "IC1") (pin "M9") (pinfunction "IO_L13P_T2_MRCC_14_M9") (pintype "bidirectional"))
      (node (ref "Y1") (pin "3") (pinfunction "OUT_3") (pintype "bidirectional"))
    )
    (net (code "56") (name "N5") (class "Default")
      (node (ref "IC1") (pin "N5") (pinfunction "M1_0_N5") (pintype "bidirectional"))
      (node (ref "R24") (pin "1") (pinfunction "1_1") (pintype "passive"))
    )
    (net (code "57") (name "Net-(C12-Pad1)") (class "Default")
      (node (ref "C12") (pin "1") (pinfunction "1_1") (pintype "passive"))
      (node (ref "C20") (pin "1") (pinfunction "1_1") (pintype "passive"))
      (node (ref "C28") (pin "1") (pinfunction "1_1") (pintype "passive"))
      (node (ref "C35") (pin "1") (pinfunction "1_1") (pintype "passive"))
      (node (ref "C4") (pin "1") (pinfunction "1_1") (pintype "passive"))
      (node (ref "C41") (pin "1") (pinfunction "1_1") (pintype "passive"))
      (node (ref "R1") (pin "1") (pinfunction "1_1") (pintype "passive"))
    )
    (net (code "58") (name "Net-(C51-Pad2)") (class "Default")
      (node (ref "C51") (pin "2") (pinfunction "2_2") (pintype "passive"))
      (node (ref "R14") (pin "2") (pinfunction "2_2") (pintype "passive"))
      (node (ref "R16") (pin "1") (pinfunction "1_1") (pintype "passive"))
    )
    (net (code "59") (name "Net-(DIS1-CONTR)") (class "Default")
      (node (ref "DIS1") (pin "3") (pinfunction "CONTR_3") (pintype "input"))
      (node (ref "VR3") (pin "WIPER") (pinfunction "S_WIPER") (pintype "passive"))
    )
    (net (code "60") (name "Net-(GS1-PadA1)") (class "Default")
      (node (ref "GS1") (pin "A1") (pinfunction "A1_A1") (pintype "bidirectional"))
      (node (ref "R46") (pin "2") (pinfunction "2_2") (pintype "passive"))
      (node (ref "R48") (pin "1") (pinfunction "1_1") (pintype "passive"))
    )
    (net (code "61") (name "Net-(IC2-EN2)") (class "Default")
      (node (ref "IC2") (pin "13") (pinfunction "EN2_13") (pintype "bidirectional"))
      (node (ref "Q3") (pin "2") (pinfunction "C_2") (pintype "passive"))
      (node (ref "R17") (pin "1") (pinfunction "1_1") (pintype "passive"))
    )
    (net (code "62") (name "Net-(IC2-MODE)") (class "Default")
      (node (ref "IC2") (pin "5") (pinfunction "MODE_5") (pintype "bidirectional"))
      (node (ref "R11") (pin "1") (pinfunction "1_1") (pintype "passive"))
      (node (ref "R12") (pin "2") (pinfunction "2_2") (pintype "passive"))
    )
    (net (code "63") (name "Net-(IC2-SW1)") (class "Default")
      (node (ref "IC2") (pin "19") (pinfunction "SW1_19") (pintype "bidirectional"))
      (node (ref "L4") (pin "P$1") (pinfunction "1_P$1") (pintype "passive"))
    )
    (net (code "64") (name "Net-(IC2-SW2)") (class "Default")
      (node (ref "IC2") (pin "2") (pinfunction "SW2_2") (pintype "bidirectional"))
      (node (ref "L3") (pin "2") (pinfunction "2_2") (pintype "passive"))
    )
    (net (code "65") (name "Net-(IC2-SW3)") (class "Default")
      (node (ref "IC2") (pin "16") (pinfunction "SW3_16") (pintype "bidirectional"))
      (node (ref "L5") (pin "1") (pinfunction "1_1") (pintype "passive"))
    )
    (net (code "66") (name "Net-(IC3-IN_A+)") (class "Default")
      (node (ref "C59") (pin "1") (pinfunction "1_1") (pintype "passive"))
      (node (ref "IC3") (pin "3") (pinfunction "IN_A+_3") (pintype "bidirectional"))
      (node (ref "R62") (pin "2") (pinfunction "2_2") (pintype "passive"))
    )
    (net (code "67") (name "Net-(IC3-IN_A-)") (class "Default")
      (node (ref "C61") (pin "+") (pinfunction "+_+") (pintype "passive"))
      (node (ref "IC3") (pin "1") (pinfunction "OUT_A_1") (pintype "bidirectional"))
      (node (ref "IC3") (pin "2") (pinfunction "IN_A-_2") (pintype "bidirectional"))
    )
    (net (code "68") (name "Net-(IC3-IN_B+)") (class "Default")
      (node (ref "C64") (pin "1") (pinfunction "1_1") (pintype "passive"))
      (node (ref "IC3") (pin "5") (pinfunction "IN_B+_5") (pintype "bidirectional"))
      (node (ref "R64") (pin "1") (pinfunction "1_1") (pintype "passive"))
    )
    (net (code "69") (name "Net-(IC3-IN_B-)") (class "Default")
      (node (ref "C66") (pin "+") (pinfunction "+_+") (pintype "passive"))
      (node (ref "IC3") (pin "6") (pinfunction "IN_B-_6") (pintype "bidirectional"))
      (node (ref "IC3") (pin "7") (pinfunction "OUT_B_7") (pintype "bidirectional"))
    )
    (net (code "70") (name "Net-(IC4-VREF)") (class "Default")
      (node (ref "C62") (pin "1") (pinfunction "1_1") (pintype "passive"))
      (node (ref "IC4") (pin "2") (pinfunction "VREF_2") (pintype "bidirectional"))
      (node (ref "VR2") (pin "WIPER") (pinfunction "S_WIPER") (pintype "passive"))
    )
    (net (code "71") (name "Net-(JP1-Pad4)") (class "Default")
      (node (ref "JP1") (pin "4") (pinfunction "4_4") (pintype "passive"))
      (node (ref "R8") (pin "1") (pinfunction "1_1") (pintype "passive"))
    )
    (net (code "72") (name "Net-(JP1-Pad6)") (class "Default")
      (node (ref "JP1") (pin "6") (pinfunction "6_6") (pintype "passive"))
      (node (ref "R10") (pin "1") (pinfunction "1_1") (pintype "passive"))
    )
    (net (code "73") (name "Net-(JP1-Pad10)") (class "Default")
      (node (ref "JP1") (pin "10") (pinfunction "10_10") (pintype "passive"))
      (node (ref "R7") (pin "1") (pinfunction "1_1") (pintype "passive"))
    )
    (net (code "74") (name "Net-(LED1-C)") (class "Default")
      (node (ref "LED1") (pin "K") (pinfunction "C_K") (pintype "passive"))
      (node (ref "R21") (pin "2") (pinfunction "2_2") (pintype "passive"))
    )
    (net (code "75") (name "Net-(LED2-PadA)") (class "Default")
      (node (ref "LED2") (pin "A") (pinfunction "A_A") (pintype "passive"))
      (node (ref "R30") (pin "1") (pinfunction "1_1") (pintype "passive"))
    )
    (net (code "76") (name "Net-(LED3-PadA)") (class "Default")
      (node (ref "LED3") (pin "A") (pinfunction "A_A") (pintype "passive"))
      (node (ref "R54") (pin "2") (pinfunction "2_2") (pintype "passive"))
    )
    (net (code "77") (name "Net-(LED4-PadA)") (class "Default")
      (node (ref "LED4") (pin "A") (pinfunction "A_A") (pintype "passive"))
      (node (ref "R55") (pin "2") (pinfunction "2_2") (pintype "passive"))
    )
    (net (code "78") (name "Net-(LED5-PadA)") (class "Default")
      (node (ref "LED5") (pin "A") (pinfunction "A_A") (pintype "passive"))
      (node (ref "R56") (pin "2") (pinfunction "2_2") (pintype "passive"))
    )
    (net (code "79") (name "Net-(LED6-PadA)") (class "Default")
      (node (ref "LED6") (pin "A") (pinfunction "A_A") (pintype "passive"))
      (node (ref "R57") (pin "2") (pinfunction "2_2") (pintype "passive"))
    )
    (net (code "80") (name "Net-(LS1-1)") (class "Default")
      (node (ref "C66") (pin "-") (pinfunction "-_-") (pintype "passive"))
      (node (ref "LS1") (pin "+") (pinfunction "1_+") (pintype "passive"))
    )
    (net (code "81") (name "Net-(LS2-1)") (class "Default")
      (node (ref "C61") (pin "-") (pinfunction "-_-") (pintype "passive"))
      (node (ref "LS2") (pin "+") (pinfunction "1_+") (pintype "passive"))
    )
    (net (code "82") (name "Net-(Q1-B)") (class "Default")
      (node (ref "D1") (pin "C") (pinfunction "C_C") (pintype "passive"))
      (node (ref "Q1") (pin "1") (pinfunction "B_1") (pintype "passive"))
      (node (ref "R4") (pin "2") (pinfunction "2_2") (pintype "passive"))
    )
    (net (code "83") (name "Net-(Q1-C)") (class "Default")
      (node (ref "Q1") (pin "2") (pinfunction "C_2") (pintype "passive"))
      (node (ref "R9") (pin "2") (pinfunction "2_2") (pintype "passive"))
    )
    (net (code "84") (name "Net-(Q2-B)") (class "Default")
      (node (ref "Q2") (pin "1") (pinfunction "B_1") (pintype "passive"))
      (node (ref "R13") (pin "2") (pinfunction "2_2") (pintype "passive"))
    )
    (net (code "85") (name "Net-(Q2-C)") (class "Default")
      (node (ref "Q2") (pin "2") (pinfunction "C_2") (pintype "passive"))
      (node (ref "Q3") (pin "1") (pinfunction "B_1") (pintype "passive"))
      (node (ref "R15") (pin "1") (pinfunction "1_1") (pintype "passive"))
    )
    (net (code "86") (name "Net-(Q4-D)") (class "Default")
      (node (ref "Q4") (pin "2") (pinfunction "D_2") (pintype "passive"))
      (node (ref "R21") (pin "1") (pinfunction "1_1") (pintype "passive"))
    )
    (net (code "87") (name "Net-(R40-Pad2)") (class "Default")
      (node (ref "R40") (pin "2") (pinfunction "2_2") (pintype "passive"))
      (node (ref "R44") (pin "2") (pinfunction "2_2") (pintype "passive"))
      (node (ref "R46") (pin "1") (pinfunction "1_1") (pintype "passive"))
    )
    (net (code "88") (name "Net-(R42-Pad2)") (class "Default")
      (node (ref "R42") (pin "2") (pinfunction "2_2") (pintype "passive"))
      (node (ref "R45") (pin "2") (pinfunction "2_2") (pintype "passive"))
      (node (ref "R47") (pin "1") (pinfunction "1_1") (pintype "passive"))
    )
    (net (code "89") (name "Net-(R50-Pad2)") (class "Default")
      (node (ref "R50") (pin "2") (pinfunction "2_2") (pintype "passive"))
      (node (ref "R58") (pin "1") (pinfunction "1_1") (pintype "passive"))
      (node (ref "SW1") (pin "P$2") (pinfunction "P$2_P$2") (pintype "passive"))
    )
    (net (code "90") (name "Net-(R51-Pad2)") (class "Default")
      (node (ref "R51") (pin "2") (pinfunction "2_2") (pintype "passive"))
      (node (ref "R59") (pin "1") (pinfunction "1_1") (pintype "passive"))
      (node (ref "SW2") (pin "P$2") (pinfunction "P$2_P$2") (pintype "passive"))
    )
    (net (code "91") (name "Net-(R52-Pad2)") (class "Default")
      (node (ref "R52") (pin "2") (pinfunction "2_2") (pintype "passive"))
      (node (ref "R60") (pin "1") (pinfunction "1_1") (pintype "passive"))
      (node (ref "SW3") (pin "P$2") (pinfunction "P$2_P$2") (pintype "passive"))
    )
    (net (code "92") (name "Net-(R53-Pad2)") (class "Default")
      (node (ref "R53") (pin "2") (pinfunction "2_2") (pintype "passive"))
      (node (ref "R61") (pin "1") (pinfunction "1_1") (pintype "passive"))
      (node (ref "SW4") (pin "P$2") (pinfunction "P$2_P$2") (pintype "passive"))
    )
    (net (code "93") (name "Net-(U1-SI(D0))") (class "Default")
      (node (ref "R37") (pin "1") (pinfunction "1_1") (pintype "passive"))
      (node (ref "U1") (pin "5") (pinfunction "SI(D0)_5") (pintype "bidirectional"))
    )
    (net (code "94") (name "Net-(U1-SO(D1))") (class "Default")
      (node (ref "R22") (pin "2") (pinfunction "2_2") (pintype "passive"))
      (node (ref "U1") (pin "2") (pinfunction "SO(D1)_2") (pintype "bidirectional"))
    )
    (net (code "95") (name "Net-(U2-DQ)") (class "Default")
      (node (ref "R47") (pin "2") (pinfunction "2_2") (pintype "passive"))
      (node (ref "R49") (pin "2") (pinfunction "2_2") (pintype "passive"))
      (node (ref "U2") (pin "2") (pinfunction "DQ_2") (pintype "bidirectional"))
    )
    (net (code "96") (name "Net-(VR1-CW)") (class "Default")
      (node (ref "R48") (pin "2") (pinfunction "2_2") (pintype "passive"))
      (node (ref "VR1") (pin "2") (pinfunction "WIPER_2") (pintype "passive"))
      (node (ref "VR1") (pin "3") (pinfunction "CW_3") (pintype "passive"))
    )
    (net (code "97") (name "PWRGD") (class "Default")
      (node (ref "IC2") (pin "4") (pinfunction "PGOOD_4") (pintype "bidirectional"))
      (node (ref "Q4") (pin "1") (pinfunction "G_1") (pintype "passive"))
      (node (ref "R20") (pin "1") (pinfunction "1_1") (pintype "passive"))
    )
    (net (code "98") (name "RS") (class "Default")
      (node (ref "DIS1") (pin "4") (pinfunction "RS_4") (pintype "input"))
      (node (ref "Q7") (pin "C") (pinfunction "D_C") (pintype "passive"))
      (node (ref "R70") (pin "1") (pinfunction "1_1") (pintype "passive"))
    )
    (net (code "99") (name "RW") (class "Default")
      (node (ref "DIS1") (pin "5") (pinfunction "R/W_5") (pintype "input"))
      (node (ref "Q10") (pin "C") (pinfunction "D_C") (pintype "passive"))
      (node (ref "R76") (pin "1") (pinfunction "1_1") (pintype "passive"))
    )
    (net (code "100") (name "TCK") (class "Default")
      (node (ref "IC1") (pin "E5") (pinfunction "TCK_0_E5") (pintype "bidirectional"))
      (node (ref "R10") (pin "2") (pinfunction "2_2") (pintype "passive"))
    )
    (net (code "101") (name "TDI") (class "Default")
      (node (ref "IC1") (pin "L4") (pinfunction "TDI_0_L4") (pintype "bidirectional"))
      (node (ref "R7") (pin "2") (pinfunction "2_2") (pintype "passive"))
    )
    (net (code "102") (name "TDO") (class "Default")
      (node (ref "IC1") (pin "K4") (pinfunction "TDO_0_K4") (pintype "bidirectional"))
      (node (ref "JP1") (pin "8") (pinfunction "8_8") (pintype "passive"))
    )
    (net (code "103") (name "TMS") (class "Default")
      (node (ref "IC1") (pin "K5") (pinfunction "TMS_0_K5") (pintype "bidirectional"))
      (node (ref "R8") (pin "2") (pinfunction "2_2") (pintype "passive"))
    )
    (net (code "104") (name "VCC1V0") (class "Default")
      (node (ref "C14") (pin "1") (pinfunction "1_1") (pintype "passive"))
      (node (ref "C16") (pin "1") (pinfunction "1_1") (pintype "passive"))
      (node (ref "C17") (pin "1") (pinfunction "1_1") (pintype "passive"))
      (node (ref "C22") (pin "1") (pinfunction "1_1") (pintype "passive"))
      (node (ref "C24") (pin "1") (pinfunction "1_1") (pintype "passive"))
      (node (ref "C25") (pin "1") (pinfunction "1_1") (pintype "passive"))
      (node (ref "C30") (pin "1") (pinfunction "1_1") (pintype "passive"))
      (node (ref "C32") (pin "1") (pinfunction "1_1") (pintype "passive"))
      (node (ref "C33") (pin "1") (pinfunction "1_1") (pintype "passive"))
      (node (ref "C37") (pin "1") (pinfunction "1_1") (pintype "passive"))
      (node (ref "C39") (pin "1") (pinfunction "1_1") (pintype "passive"))
      (node (ref "C51") (pin "1") (pinfunction "1_1") (pintype "passive"))
      (node (ref "C52") (pin "1") (pinfunction "1_1") (pintype "passive"))
      (node (ref "C6") (pin "1") (pinfunction "1_1") (pintype "passive"))
      (node (ref "C8") (pin "1") (pinfunction "1_1") (pintype "passive"))
      (node (ref "C9") (pin "1") (pinfunction "1_1") (pintype "passive"))
      (node (ref "IC1") (pin "E10") (pinfunction "VCCINT_2_E10") (pintype "bidirectional"))
      (node (ref "IC1") (pin "E8") (pinfunction "VCCINT_1_E8") (pintype "bidirectional"))
      (node (ref "IC1") (pin "F7") (pinfunction "VCCINT_3_F7") (pintype "bidirectional"))
      (node (ref "IC1") (pin "G10") (pinfunction "VCCINT_4_G10") (pintype "bidirectional"))
      (node (ref "IC1") (pin "G6") (pinfunction "VCCBRAM_1_G6") (pintype "bidirectional"))
      (node (ref "IC1") (pin "H7") (pinfunction "VCCINT_5_H7") (pintype "bidirectional"))
      (node (ref "IC1") (pin "J10") (pinfunction "VCCINT_6_J10") (pintype "bidirectional"))
      (node (ref "IC1") (pin "J6") (pinfunction "VCCBRAM_2_J6") (pintype "bidirectional"))
      (node (ref "IC1") (pin "K7") (pinfunction "VCCINT_7_K7") (pintype "bidirectional"))
      (node (ref "IC1") (pin "K9") (pinfunction "VCCINT_8_K9") (pintype "bidirectional"))
      (node (ref "L4") (pin "P$2") (pinfunction "2_P$2") (pintype "passive"))
      (node (ref "R13") (pin "1") (pinfunction "1_1") (pintype "passive"))
      (node (ref "R14") (pin "1") (pinfunction "1_1") (pintype "passive"))
    )
    (net (code "105") (name "VCC1V8") (class "Default")
      (node (ref "C15") (pin "1") (pinfunction "1_1") (pintype "passive"))
      (node (ref "C23") (pin "1") (pinfunction "1_1") (pintype "passive"))
      (node (ref "C31") (pin "1") (pinfunction "1_1") (pintype "passive"))
      (node (ref "C38") (pin "1") (pinfunction "1_1") (pintype "passive"))
      (node (ref "C43") (pin "1") (pinfunction "1_1") (pintype "passive"))
      (node (ref "C49") (pin "1") (pinfunction "1_1") (pintype "passive"))
      (node (ref "C50") (pin "1") (pinfunction "1_1") (pintype "passive"))
      (node (ref "C7") (pin "1") (pinfunction "1_1") (pintype "passive"))
      (node (ref "IC1") (pin "D5") (pinfunction "VCCBATT_0_D5") (pintype "bidirectional"))
      (node (ref "IC1") (pin "L6") (pinfunction "VCCAUX_1_L6") (pintype "bidirectional"))
      (node (ref "IC1") (pin "L8") (pinfunction "VCCAUX_2_L8") (pintype "bidirectional"))
      (node (ref "L2") (pin "2") (pinfunction "2_2") (pintype "passive"))
      (node (ref "L3") (pin "1") (pinfunction "1_1") (pintype "passive"))
      (node (ref "R2") (pin "2") (pinfunction "2_2") (pintype "passive"))
      (node (ref "R6") (pin "2") (pinfunction "2_2") (pintype "passive"))
    )
    (net (code "106") (name "VCC3V3") (class "Default")
      (node (ref "C1") (pin "1") (pinfunction "1_1") (pintype "passive"))
      (node (ref "C10") (pin "1") (pinfunction "1_1") (pintype "passive"))
      (node (ref "C11") (pin "1") (pinfunction "1_1") (pintype "passive"))
      (node (ref "C13") (pin "1") (pinfunction "1_1") (pintype "passive"))
      (node (ref "C19") (pin "1") (pinfunction "1_1") (pintype "passive"))
      (node (ref "C2") (pin "1") (pinfunction "1_1") (pintype "passive"))
      (node (ref "C21") (pin "1") (pinfunction "1_1") (pintype "passive"))
      (node (ref "C27") (pin "1") (pinfunction "1_1") (pintype "passive"))
      (node (ref "C29") (pin "1") (pinfunction "1_1") (pintype "passive"))
      (node (ref "C3") (pin "1") (pinfunction "1_1") (pintype "passive"))
      (node (ref "C34") (pin "1") (pinfunction "1_1") (pintype "passive"))
      (node (ref "C36") (pin "1") (pinfunction "1_1") (pintype "passive"))
      (node (ref "C40") (pin "1") (pinfunction "1_1") (pintype "passive"))
      (node (ref "C42") (pin "1") (pinfunction "1_1") (pintype "passive"))
      (node (ref "C44") (pin "1") (pinfunction "1_1") (pintype "passive"))
      (node (ref "C45") (pin "1") (pinfunction "1_1") (pintype "passive"))
      (node (ref "C46") (pin "1") (pinfunction "1_1") (pintype "passive"))
      (node (ref "C47") (pin "1") (pinfunction "1_1") (pintype "passive"))
      (node (ref "C48") (pin "1") (pinfunction "1_1") (pintype "passive"))
      (node (ref "C5") (pin "1") (pinfunction "1_1") (pintype "passive"))
      (node (ref "C53") (pin "1") (pinfunction "1_1") (pintype "passive"))
      (node (ref "C54") (pin "1") (pinfunction "1_1") (pintype "passive"))
      (node (ref "C55") (pin "1") (pinfunction "1_1") (pintype "passive"))
      (node (ref "C58") (pin "1") (pinfunction "1_1") (pintype "passive"))
      (node (ref "C60") (pin "1") (pinfunction "1_1") (pintype "passive"))
      (node (ref "C63") (pin "1") (pinfunction "1_1") (pintype "passive"))
      (node (ref "C65") (pin "1") (pinfunction "1_1") (pintype "passive"))
      (node (ref "C67") (pin "1") (pinfunction "1_1") (pintype "passive"))
      (node (ref "C68") (pin "1") (pinfunction "1_1") (pintype "passive"))
      (node (ref "C69") (pin "1") (pinfunction "1_1") (pintype "passive"))
      (node (ref "C70") (pin "1") (pinfunction "1_1") (pintype "passive"))
      (node (ref "C71") (pin "1") (pinfunction "1_1") (pintype "passive"))
      (node (ref "DIS1") (pin "2") (pinfunction "VCC_2") (pintype "power_in"))
      (node (ref "GS1") (pin "B1") (pinfunction "B1_B1") (pintype "bidirectional"))
      (node (ref "GS1") (pin "HB") (pinfunction "H2_HB") (pintype "bidirectional"))
      (node (ref "IC1") (pin "B7") (pinfunction "VCCO_15_1_B7") (pintype "bidirectional"))
      (node (ref "IC1") (pin "C11") (pinfunction "VCCO_15_2_C11") (pintype "bidirectional"))
      (node (ref "IC1") (pin "C3") (pinfunction "VCCO_34_1_C3") (pintype "bidirectional"))
      (node (ref "IC1") (pin "E6") (pinfunction "VCCO_0_1_E6") (pintype "bidirectional"))
      (node (ref "IC1") (pin "F12") (pinfunction "VCCO_15_3_F12") (pintype "bidirectional"))
      (node (ref "IC1") (pin "G2") (pinfunction "VCCO_34_2_G2") (pintype "bidirectional"))
      (node (ref "IC1") (pin "J14") (pinfunction "VCCO_14_1_J14") (pintype "bidirectional"))
      (node (ref "IC1") (pin "L3") (pinfunction "VCCO_34_3_L3") (pintype "bidirectional"))
      (node (ref "IC1") (pin "M12") (pinfunction "VCCO_14_2_M12") (pintype "bidirectional"))
      (node (ref "IC1") (pin "P5") (pinfunction "VCCO_0_2_P5") (pintype "bidirectional"))
      (node (ref "IC1") (pin "P9") (pinfunction "VCCO_14_3_P9") (pintype "bidirectional"))
      (node (ref "IC2") (pin "10") (pinfunction "SVIN_10") (pintype "bidirectional"))
      (node (ref "IC2") (pin "14") (pinfunction "EN1_14") (pintype "bidirectional"))
      (node (ref "IC2") (pin "17") (pinfunction "PVIN3_17") (pintype "bidirectional"))
      (node (ref "IC2") (pin "18") (pinfunction "PVIN1_18") (pintype "bidirectional"))
      (node (ref "IC2") (pin "6") (pinfunction "RT_6") (pintype "bidirectional"))
      (node (ref "IC3") (pin "8") (pinfunction "V+_8") (pintype "bidirectional"))
      (node (ref "IC4") (pin "1") (pinfunction "VDD_1") (pintype "bidirectional"))
      (node (ref "JP1") (pin "2") (pinfunction "2_2") (pintype "passive"))
      (node (ref "L5") (pin "2") (pinfunction "2_2") (pintype "passive"))
      (node (ref "LED1") (pin "A") (pinfunction "A_A") (pintype "passive"))
      (node (ref "Q1") (pin "3") (pinfunction "E_3") (pintype "passive"))
      (node (ref "Q11") (pin "B") (pinfunction "G_B") (pintype "passive"))
      (node (ref "Q12") (pin "B") (pinfunction "G_B") (pintype "passive"))
      (node (ref "Q14") (pin "B") (pinfunction "G_B") (pintype "passive"))
      (node (ref "Q15") (pin "B") (pinfunction "G_B") (pintype "passive"))
      (node (ref "Q5") (pin "B") (pinfunction "G_B") (pintype "passive"))
      (node (ref "Q6") (pin "B") (pinfunction "G_B") (pintype "passive"))
      (node (ref "Q8") (pin "B") (pinfunction "G_B") (pintype "passive"))
      (node (ref "Q9") (pin "B") (pinfunction "G_B") (pintype "passive"))
      (node (ref "R1") (pin "2") (pinfunction "2_2") (pintype "passive"))
      (node (ref "R15") (pin "2") (pinfunction "2_2") (pintype "passive"))
      (node (ref "R17") (pin "2") (pinfunction "2_2") (pintype "passive"))
      (node (ref "R18") (pin "1") (pinfunction "1_1") (pintype "passive"))
      (node (ref "R20") (pin "2") (pinfunction "2_2") (pintype "passive"))
      (node (ref "R23") (pin "2") (pinfunction "2_2") (pintype "passive"))
      (node (ref "R25") (pin "2") (pinfunction "2_2") (pintype "passive"))
      (node (ref "R26") (pin "2") (pinfunction "2_2") (pintype "passive"))
      (node (ref "R28") (pin "2") (pinfunction "2_2") (pintype "passive"))
      (node (ref "R29") (pin "2") (pinfunction "2_2") (pintype "passive"))
      (node (ref "R31") (pin "2") (pinfunction "2_2") (pintype "passive"))
      (node (ref "R32") (pin "2") (pinfunction "2_2") (pintype "passive"))
      (node (ref "R33") (pin "2") (pinfunction "2_2") (pintype "passive"))
      (node (ref "R35") (pin "2") (pinfunction "2_2") (pintype "passive"))
      (node (ref "R38") (pin "2") (pinfunction "2_2") (pintype "passive"))
      (node (ref "R4") (pin "1") (pinfunction "1_1") (pintype "passive"))
      (node (ref "R49") (pin "1") (pinfunction "1_1") (pintype "passive"))
      (node (ref "R63") (pin "1") (pinfunction "1_1") (pintype "passive"))
      (node (ref "R65") (pin "2") (pinfunction "2_2") (pintype "passive"))
      (node (ref "R66") (pin "2") (pinfunction "2_2") (pintype "passive"))
      (node (ref "R67") (pin "2") (pinfunction "2_2") (pintype "passive"))
      (node (ref "R68") (pin "2") (pinfunction "2_2") (pintype "passive"))
      (node (ref "R69") (pin "2") (pinfunction "2_2") (pintype "passive"))
      (node (ref "R70") (pin "2") (pinfunction "2_2") (pintype "passive"))
      (node (ref "R71") (pin "2") (pinfunction "2_2") (pintype "passive"))
      (node (ref "R72") (pin "2") (pinfunction "2_2") (pintype "passive"))
      (node (ref "R73") (pin "2") (pinfunction "2_2") (pintype "passive"))
      (node (ref "R74") (pin "2") (pinfunction "2_2") (pintype "passive"))
      (node (ref "R75") (pin "2") (pinfunction "2_2") (pintype "passive"))
      (node (ref "R76") (pin "2") (pinfunction "2_2") (pintype "passive"))
      (node (ref "R77") (pin "2") (pinfunction "2_2") (pintype "passive"))
      (node (ref "R78") (pin "2") (pinfunction "2_2") (pintype "passive"))
      (node (ref "R79") (pin "2") (pinfunction "2_2") (pintype "passive"))
      (node (ref "R80") (pin "2") (pinfunction "2_2") (pintype "passive"))
      (node (ref "R81") (pin "2") (pinfunction "2_2") (pintype "passive"))
      (node (ref "R82") (pin "2") (pinfunction "2_2") (pintype "passive"))
      (node (ref "R83") (pin "2") (pinfunction "2_2") (pintype "passive"))
      (node (ref "R84") (pin "2") (pinfunction "2_2") (pintype "passive"))
      (node (ref "R85") (pin "2") (pinfunction "2_2") (pintype "passive"))
      (node (ref "R86") (pin "2") (pinfunction "2_2") (pintype "passive"))
      (node (ref "SW1") (pin "P$1") (pinfunction "P$1_P$1") (pintype "passive"))
      (node (ref "SW2") (pin "P$1") (pinfunction "P$1_P$1") (pintype "passive"))
      (node (ref "SW3") (pin "P$1") (pinfunction "P$1_P$1") (pintype "passive"))
      (node (ref "SW4") (pin "P$1") (pinfunction "P$1_P$1") (pintype "passive"))
      (node (ref "U1") (pin "8") (pinfunction "VCC_8") (pintype "bidirectional"))
      (node (ref "U2") (pin "3") (pinfunction "VDD_3") (pintype "power_in"))
      (node (ref "VR2") (pin "TOP") (pinfunction "E_TOP") (pintype "passive"))
      (node (ref "VR3") (pin "TOP") (pinfunction "E_TOP") (pintype "passive"))
      (node (ref "Y1") (pin "1") (pinfunction "~{ST}_1") (pintype "bidirectional"))
      (node (ref "Y1") (pin "4") (pinfunction "VCC_4") (pintype "bidirectional"))
    )
    (net (code "107") (name "VD") (class "Default")
      (node (ref "IC2") (pin "3") (pinfunction "PVIN2_3") (pintype "bidirectional"))
      (node (ref "R11") (pin "2") (pinfunction "2_2") (pintype "passive"))
    )
    (net (code "108") (name "WP") (class "Default")
      (node (ref "R36") (pin "2") (pinfunction "2_2") (pintype "passive"))
      (node (ref "R38") (pin "1") (pinfunction "1_1") (pintype "passive"))
      (node (ref "U1") (pin "3") (pinfunction "~{WP}(D2)_3") (pintype "bidirectional"))
    )
    (net (code "109") (name "XADCGND") (class "Default")
      (node (ref "C18") (pin "2") (pinfunction "2_2") (pintype "passive"))
      (node (ref "IC1") (pin "F8") (pinfunction "GNDADC_0_F8") (pintype "bidirectional"))
      (node (ref "IC1") (pin "G8") (pinfunction "VREFN_0_G8") (pintype "bidirectional"))
      (node (ref "IC1") (pin "G9") (pinfunction "VP_0_G9") (pintype "bidirectional"))
      (node (ref "IC1") (pin "H8") (pinfunction "VN_0_H8") (pintype "bidirectional"))
      (node (ref "IC1") (pin "H9") (pinfunction "VREFP_0_H9") (pintype "bidirectional"))
      (node (ref "L1") (pin "2") (pinfunction "2_2") (pintype "passive"))
    )
    (net (code "110") (name "XADCVCC") (class "Default")
      (node (ref "C18") (pin "1") (pinfunction "1_1") (pintype "passive"))
      (node (ref "C26") (pin "1") (pinfunction "1_1") (pintype "passive"))
      (node (ref "IC1") (pin "F9") (pinfunction "VCCADC_0_F9") (pintype "bidirectional"))
      (node (ref "L2") (pin "1") (pinfunction "1_1") (pintype "passive"))
    )
    (net (code "111") (name "unconnected-(DIS1-NC-Pad15)") (class "Default")
      (node (ref "DIS1") (pin "15") (pinfunction "NC_15") (pintype "no_connect"))
    )
    (net (code "112") (name "unconnected-(DIS1-NC-Pad16)") (class "Default")
      (node (ref "DIS1") (pin "16") (pinfunction "NC_16") (pintype "no_connect"))
    )
    (net (code "113") (name "unconnected-(IC1-IO_0_14-PadJ11)") (class "Default")
      (node (ref "IC1") (pin "J11") (pinfunction "IO_0_14_J11") (pintype "bidirectional"))
    )
    (net (code "114") (name "unconnected-(IC1-IO_0_15-PadD11)") (class "Default")
      (node (ref "IC1") (pin "D11") (pinfunction "IO_0_15_D11") (pintype "bidirectional"))
    )
    (net (code "115") (name "unconnected-(IC1-IO_0_34-PadG4)") (class "Default")
      (node (ref "IC1") (pin "G4") (pinfunction "IO_0_34_G4") (pintype "bidirectional"))
    )
    (net (code "116") (name "unconnected-(IC1-IO_25_14-PadL10)") (class "Default")
      (node (ref "IC1") (pin "L10") (pinfunction "IO_25_14_L10") (pintype "bidirectional"))
    )
    (net (code "117") (name "unconnected-(IC1-IO_25_15-PadH11)") (class "Default")
      (node (ref "IC1") (pin "H11") (pinfunction "IO_25_15_H11") (pintype "bidirectional"))
    )
    (net (code "118") (name "unconnected-(IC1-IO_25_34-PadN4)") (class "Default")
      (node (ref "IC1") (pin "N4") (pinfunction "IO_25_34_N4") (pintype "bidirectional"))
    )
    (net (code "119") (name "unconnected-(IC1-IO_L1P_T0_34-PadA4)") (class "Default")
      (node (ref "IC1") (pin "A4") (pinfunction "IO_L1P_T0_34_A4") (pintype "bidirectional"))
    )
    (net (code "120") (name "unconnected-(IC1-IO_L2N_T0_AD8N_15-PadD8)") (class "Default")
      (node (ref "IC1") (pin "D8") (pinfunction "IO_L2N_T0_AD8N_15_D8") (pintype "bidirectional"))
    )
    (net (code "121") (name "unconnected-(IC1-IO_L2P_T0_AD8P_15-PadD7)") (class "Default")
      (node (ref "IC1") (pin "D7") (pinfunction "IO_L2P_T0_AD8P_15_D7") (pintype "bidirectional"))
    )
    (net (code "122") (name "unconnected-(IC1-IO_L3N_T0_DQS_34-PadB3)") (class "Default")
      (node (ref "IC1") (pin "B3") (pinfunction "IO_L3N_T0_DQS_34_B3") (pintype "bidirectional"))
    )
    (net (code "123") (name "unconnected-(IC1-IO_L3N_T0_DQS_AD1N_15-PadA7)") (class "Default")
      (node (ref "IC1") (pin "A7") (pinfunction "IO_L3N_T0_DQS_AD1N_15_A7") (pintype "bidirectional"))
    )
    (net (code "124") (name "unconnected-(IC1-IO_L3P_T0_DQS_34-PadB4)") (class "Default")
      (node (ref "IC1") (pin "B4") (pinfunction "IO_L3P_T0_DQS_34_B4") (pintype "bidirectional"))
    )
    (net (code "125") (name "unconnected-(IC1-IO_L3P_T0_DQS_AD1P_15-PadB6)") (class "Default")
      (node (ref "IC1") (pin "B6") (pinfunction "IO_L3P_T0_DQS_AD1P_15_B6") (pintype "bidirectional"))
    )
    (net (code "126") (name "unconnected-(IC1-IO_L4N_T0_AD9N_15-PadC9)") (class "Default")
      (node (ref "IC1") (pin "C9") (pinfunction "IO_L4N_T0_AD9N_15_C9") (pintype "bidirectional"))
    )
    (net (code "127") (name "unconnected-(IC1-IO_L4N_T0_D05_14-PadL15)") (class "Default")
      (node (ref "IC1") (pin "L15") (pinfunction "IO_L4N_T0_D05_14_L15") (pintype "bidirectional"))
    )
    (net (code "128") (name "unconnected-(IC1-IO_L4P_T0_34-PadC1)") (class "Default")
      (node (ref "IC1") (pin "C1") (pinfunction "IO_L4P_T0_34_C1") (pintype "bidirectional"))
    )
    (net (code "129") (name "unconnected-(IC1-IO_L4P_T0_D04_14-PadK14)") (class "Default")
      (node (ref "IC1") (pin "K14") (pinfunction "IO_L4P_T0_D04_14_K14") (pintype "bidirectional"))
    )
    (net (code "130") (name "unconnected-(IC1-IO_L5N_T0_34-PadB5)") (class "Default")
      (node (ref "IC1") (pin "B5") (pinfunction "IO_L5N_T0_34_B5") (pintype "bidirectional"))
    )
    (net (code "131") (name "unconnected-(IC1-IO_L5N_T0_AD2N_15-PadA6)") (class "Default")
      (node (ref "IC1") (pin "A6") (pinfunction "IO_L5N_T0_AD2N_15_A6") (pintype "bidirectional"))
    )
    (net (code "132") (name "unconnected-(IC1-IO_L5N_T0_D07_14-PadK15)") (class "Default")
      (node (ref "IC1") (pin "K15") (pinfunction "IO_L5N_T0_D07_14_K15") (pintype "bidirectional"))
    )
    (net (code "133") (name "unconnected-(IC1-IO_L5P_T0_AD2P_15-PadA5)") (class "Default")
      (node (ref "IC1") (pin "A5") (pinfunction "IO_L5P_T0_AD2P_15_A5") (pintype "bidirectional"))
    )
    (net (code "134") (name "unconnected-(IC1-IO_L5P_T0_D06_14-PadJ15)") (class "Default")
      (node (ref "IC1") (pin "J15") (pinfunction "IO_L5P_T0_D06_14_J15") (pintype "bidirectional"))
    )
    (net (code "135") (name "unconnected-(IC1-IO_L6N_T0_D08_VREF_14-PadL12)") (class "Default")
      (node (ref "IC1") (pin "L12") (pinfunction "IO_L6N_T0_D08_VREF_14_L12") (pintype "bidirectional"))
    )
    (net (code "136") (name "unconnected-(IC1-IO_L6N_T0_VREF_15-PadA9)") (class "Default")
      (node (ref "IC1") (pin "A9") (pinfunction "IO_L6N_T0_VREF_15_A9") (pintype "bidirectional"))
    )
    (net (code "137") (name "unconnected-(IC1-IO_L6P_T0_15-PadA8)") (class "Default")
      (node (ref "IC1") (pin "A8") (pinfunction "IO_L6P_T0_15_A8") (pintype "bidirectional"))
    )
    (net (code "138") (name "unconnected-(IC1-IO_L7N_T1_34-PadC4)") (class "Default")
      (node (ref "IC1") (pin "C4") (pinfunction "IO_L7N_T1_34_C4") (pintype "bidirectional"))
    )
    (net (code "139") (name "unconnected-(IC1-IO_L7N_T1_AD10N_15-PadD10)") (class "Default")
      (node (ref "IC1") (pin "D10") (pinfunction "IO_L7N_T1_AD10N_15_D10") (pintype "bidirectional"))
    )
    (net (code "140") (name "unconnected-(IC1-IO_L7N_T1_D10_14-PadL14)") (class "Default")
      (node (ref "IC1") (pin "L14") (pinfunction "IO_L7N_T1_D10_14_L14") (pintype "bidirectional"))
    )
    (net (code "141") (name "unconnected-(IC1-IO_L7P_T1_34-PadD4)") (class "Default")
      (node (ref "IC1") (pin "D4") (pinfunction "IO_L7P_T1_34_D4") (pintype "bidirectional"))
    )
    (net (code "142") (name "unconnected-(IC1-IO_L7P_T1_AD10P_15-PadD9)") (class "Default")
      (node (ref "IC1") (pin "D9") (pinfunction "IO_L7P_T1_AD10P_15_D9") (pintype "bidirectional"))
    )
    (net (code "143") (name "unconnected-(IC1-IO_L7P_T1_D09_14-PadL13)") (class "Default")
      (node (ref "IC1") (pin "L13") (pinfunction "IO_L7P_T1_D09_14_L13") (pintype "bidirectional"))
    )
    (net (code "144") (name "unconnected-(IC1-IO_L8N_T1_D12_14-PadN13)") (class "Default")
      (node (ref "IC1") (pin "N13") (pinfunction "IO_L8N_T1_D12_14_N13") (pintype "bidirectional"))
    )
    (net (code "145") (name "unconnected-(IC1-IO_L8P_T1_AD3P_15-PadC10)") (class "Default")
      (node (ref "IC1") (pin "C10") (pinfunction "IO_L8P_T1_AD3P_15_C10") (pintype "bidirectional"))
    )
    (net (code "146") (name "unconnected-(IC1-IO_L8P_T1_D11_14-PadM13)") (class "Default")
      (node (ref "IC1") (pin "M13") (pinfunction "IO_L8P_T1_D11_14_M13") (pintype "bidirectional"))
    )
    (net (code "147") (name "unconnected-(IC1-IO_L9N_T1_DQS_34-PadD3)") (class "Default")
      (node (ref "IC1") (pin "D3") (pinfunction "IO_L9N_T1_DQS_34_D3") (pintype "bidirectional"))
    )
    (net (code "148") (name "unconnected-(IC1-IO_L9N_T1_DQS_AD11N_15-PadA10)") (class "Default")
      (node (ref "IC1") (pin "A10") (pinfunction "IO_L9N_T1_DQS_AD11N_15_A10") (pintype "bidirectional"))
    )
    (net (code "149") (name "unconnected-(IC1-IO_L9N_T1_DQS_D13_14-PadM15)") (class "Default")
      (node (ref "IC1") (pin "M15") (pinfunction "IO_L9N_T1_DQS_D13_14_M15") (pintype "bidirectional"))
    )
    (net (code "150") (name "unconnected-(IC1-IO_L9P_T1_DQS_14-PadM14)") (class "Default")
      (node (ref "IC1") (pin "M14") (pinfunction "IO_L9P_T1_DQS_14_M14") (pintype "bidirectional"))
    )
    (net (code "151") (name "unconnected-(IC1-IO_L9P_T1_DQS_34-PadE3)") (class "Default")
      (node (ref "IC1") (pin "E3") (pinfunction "IO_L9P_T1_DQS_34_E3") (pintype "bidirectional"))
    )
    (net (code "152") (name "unconnected-(IC1-IO_L9P_T1_DQS_AD11P_15-PadB9)") (class "Default")
      (node (ref "IC1") (pin "B9") (pinfunction "IO_L9P_T1_DQS_AD11P_15_B9") (pintype "bidirectional"))
    )
    (net (code "153") (name "unconnected-(IC1-IO_L10N_T1_34-PadF1)") (class "Default")
      (node (ref "IC1") (pin "F1") (pinfunction "IO_L10N_T1_34_F1") (pintype "bidirectional"))
    )
    (net (code "154") (name "unconnected-(IC1-IO_L10N_T1_D15_14-PadN15)") (class "Default")
      (node (ref "IC1") (pin "N15") (pinfunction "IO_L10N_T1_D15_14_N15") (pintype "bidirectional"))
    )
    (net (code "155") (name "unconnected-(IC1-IO_L10P_T1_34-PadF2)") (class "Default")
      (node (ref "IC1") (pin "F2") (pinfunction "IO_L10P_T1_34_F2") (pintype "bidirectional"))
    )
    (net (code "156") (name "unconnected-(IC1-IO_L10P_T1_D14_14-PadN14)") (class "Default")
      (node (ref "IC1") (pin "N14") (pinfunction "IO_L10P_T1_D14_14_N14") (pintype "bidirectional"))
    )
    (net (code "157") (name "unconnected-(IC1-IO_L11N_T1_SRCC_14-PadP15)") (class "Default")
      (node (ref "IC1") (pin "P15") (pinfunction "IO_L11N_T1_SRCC_14_P15") (pintype "bidirectional"))
    )
    (net (code "158") (name "unconnected-(IC1-IO_L11N_T1_SRCC_34-PadF3)") (class "Default")
      (node (ref "IC1") (pin "F3") (pinfunction "IO_L11N_T1_SRCC_34_F3") (pintype "bidirectional"))
    )
    (net (code "159") (name "unconnected-(IC1-IO_L11P_T1_SRCC_14-PadP14)") (class "Default")
      (node (ref "IC1") (pin "P14") (pinfunction "IO_L11P_T1_SRCC_14_P14") (pintype "bidirectional"))
    )
    (net (code "160") (name "unconnected-(IC1-IO_L11P_T1_SRCC_34-PadF4)") (class "Default")
      (node (ref "IC1") (pin "F4") (pinfunction "IO_L11P_T1_SRCC_34_F4") (pintype "bidirectional"))
    )
    (net (code "161") (name "unconnected-(IC1-IO_L12N_T1_MRCC_14-PadR14)") (class "Default")
      (node (ref "IC1") (pin "R14") (pinfunction "IO_L12N_T1_MRCC_14_R14") (pintype "bidirectional"))
    )
    (net (code "162") (name "unconnected-(IC1-IO_L12N_T1_MRCC_34-PadG1)") (class "Default")
      (node (ref "IC1") (pin "G1") (pinfunction "IO_L12N_T1_MRCC_34_G1") (pintype "bidirectional"))
    )
    (net (code "163") (name "unconnected-(IC1-IO_L12P_T1_MRCC_14-PadR13)") (class "Default")
      (node (ref "IC1") (pin "R13") (pinfunction "IO_L12P_T1_MRCC_14_R13") (pintype "bidirectional"))
    )
    (net (code "164") (name "unconnected-(IC1-IO_L12P_T1_MRCC_34-PadH1)") (class "Default")
      (node (ref "IC1") (pin "H1") (pinfunction "IO_L12P_T1_MRCC_34_H1") (pintype "bidirectional"))
    )
    (net (code "165") (name "unconnected-(IC1-IO_L13N_T2_MRCC_14-PadM10)") (class "Default")
      (node (ref "IC1") (pin "M10") (pinfunction "IO_L13N_T2_MRCC_14_M10") (pintype "bidirectional"))
    )
    (net (code "166") (name "unconnected-(IC1-IO_L13N_T2_MRCC_15-PadB14)") (class "Default")
      (node (ref "IC1") (pin "B14") (pinfunction "IO_L13N_T2_MRCC_15_B14") (pintype "bidirectional"))
    )
    (net (code "167") (name "unconnected-(IC1-IO_L13N_T2_MRCC_34-PadH3)") (class "Default")
      (node (ref "IC1") (pin "H3") (pinfunction "IO_L13N_T2_MRCC_34_H3") (pintype "bidirectional"))
    )
    (net (code "168") (name "unconnected-(IC1-IO_L13P_T2_MRCC_15-PadB13)") (class "Default")
      (node (ref "IC1") (pin "B13") (pinfunction "IO_L13P_T2_MRCC_15_B13") (pintype "bidirectional"))
    )
    (net (code "169") (name "unconnected-(IC1-IO_L13P_T2_MRCC_34-PadH4)") (class "Default")
      (node (ref "IC1") (pin "H4") (pinfunction "IO_L13P_T2_MRCC_34_H4") (pintype "bidirectional"))
    )
    (net (code "170") (name "unconnected-(IC1-IO_L14N_T2_SRCC_14-PadP12)") (class "Default")
      (node (ref "IC1") (pin "P12") (pinfunction "IO_L14N_T2_SRCC_14_P12") (pintype "bidirectional"))
    )
    (net (code "171") (name "unconnected-(IC1-IO_L14N_T2_SRCC_15-PadB15)") (class "Default")
      (node (ref "IC1") (pin "B15") (pinfunction "IO_L14N_T2_SRCC_15_B15") (pintype "bidirectional"))
    )
    (net (code "172") (name "unconnected-(IC1-IO_L14N_T2_SRCC_34-PadH2)") (class "Default")
      (node (ref "IC1") (pin "H2") (pinfunction "IO_L14N_T2_SRCC_34_H2") (pintype "bidirectional"))
    )
    (net (code "173") (name "unconnected-(IC1-IO_L14P_T2_SRCC_14-PadN12)") (class "Default")
      (node (ref "IC1") (pin "N12") (pinfunction "IO_L14P_T2_SRCC_14_N12") (pintype "bidirectional"))
    )
    (net (code "174") (name "unconnected-(IC1-IO_L14P_T2_SRCC_15-PadC15)") (class "Default")
      (node (ref "IC1") (pin "C15") (pinfunction "IO_L14P_T2_SRCC_15_C15") (pintype "bidirectional"))
    )
    (net (code "175") (name "unconnected-(IC1-IO_L14P_T2_SRCC_34-PadJ2)") (class "Default")
      (node (ref "IC1") (pin "J2") (pinfunction "IO_L14P_T2_SRCC_34_J2") (pintype "bidirectional"))
    )
    (net (code "176") (name "unconnected-(IC1-IO_L15N_T2_DQS_15-PadC14)") (class "Default")
      (node (ref "IC1") (pin "C14") (pinfunction "IO_L15N_T2_DQS_15_C14") (pintype "bidirectional"))
    )
    (net (code "177") (name "unconnected-(IC1-IO_L15N_T2_DQS_34-PadJ3)") (class "Default")
      (node (ref "IC1") (pin "J3") (pinfunction "IO_L15N_T2_DQS_34_J3") (pintype "bidirectional"))
    )
    (net (code "178") (name "unconnected-(IC1-IO_L15N_T2_DQS_DOUT_CSO_B_14-PadN11)") (class "Default")
      (node (ref "IC1") (pin "N11") (pinfunction "IO_L15N_T2_DQS_DOUT_CSO_B_14_N11") (pintype "bidirectional"))
    )
    (net (code "179") (name "unconnected-(IC1-IO_L15P_T2_DQS_15-PadC13)") (class "Default")
      (node (ref "IC1") (pin "C13") (pinfunction "IO_L15P_T2_DQS_15_C13") (pintype "bidirectional"))
    )
    (net (code "180") (name "unconnected-(IC1-IO_L15P_T2_DQS_34-PadJ4)") (class "Default")
      (node (ref "IC1") (pin "J4") (pinfunction "IO_L15P_T2_DQS_34_J4") (pintype "bidirectional"))
    )
    (net (code "181") (name "unconnected-(IC1-IO_L15P_T2_DQS_RDWR_B_14-PadN10)") (class "Default")
      (node (ref "IC1") (pin "N10") (pinfunction "IO_L15P_T2_DQS_RDWR_B_14_N10") (pintype "bidirectional"))
    )
    (net (code "182") (name "unconnected-(IC1-IO_L16N_T2_15-PadD13)") (class "Default")
      (node (ref "IC1") (pin "D13") (pinfunction "IO_L16N_T2_15_D13") (pintype "bidirectional"))
    )
    (net (code "183") (name "unconnected-(IC1-IO_L16N_T2_D31_14-PadP11)") (class "Default")
      (node (ref "IC1") (pin "P11") (pinfunction "IO_L16N_T2_D31_14_P11") (pintype "bidirectional"))
    )
    (net (code "184") (name "unconnected-(IC1-IO_L16P_T2_15-PadD12)") (class "Default")
      (node (ref "IC1") (pin "D12") (pinfunction "IO_L16P_T2_15_D12") (pintype "bidirectional"))
    )
    (net (code "185") (name "unconnected-(IC1-IO_L16P_T2_CSI_B_14-PadP10)") (class "Default")
      (node (ref "IC1") (pin "P10") (pinfunction "IO_L16P_T2_CSI_B_14_P10") (pintype "bidirectional"))
    )
    (net (code "186") (name "unconnected-(IC1-IO_L17N_T2_D29_14-PadR10)") (class "Default")
      (node (ref "IC1") (pin "R10") (pinfunction "IO_L17N_T2_D29_14_R10") (pintype "bidirectional"))
    )
    (net (code "187") (name "unconnected-(IC1-IO_L17P_T2_15-PadF11)") (class "Default")
      (node (ref "IC1") (pin "F11") (pinfunction "IO_L17P_T2_15_F11") (pintype "bidirectional"))
    )
    (net (code "188") (name "unconnected-(IC1-IO_L17P_T2_D30_14-PadR9)") (class "Default")
      (node (ref "IC1") (pin "R9") (pinfunction "IO_L17P_T2_D30_14_R9") (pintype "bidirectional"))
    )
    (net (code "189") (name "unconnected-(IC1-IO_L18N_T2_34-PadL1)") (class "Default")
      (node (ref "IC1") (pin "L1") (pinfunction "IO_L18N_T2_34_L1") (pintype "bidirectional"))
    )
    (net (code "190") (name "unconnected-(IC1-IO_L18N_T2_D27_14-PadR12)") (class "Default")
      (node (ref "IC1") (pin "R12") (pinfunction "IO_L18N_T2_D27_14_R12") (pintype "bidirectional"))
    )
    (net (code "191") (name "unconnected-(IC1-IO_L18P_T2_34-PadM1)") (class "Default")
      (node (ref "IC1") (pin "M1") (pinfunction "IO_L18P_T2_34_M1") (pintype "bidirectional"))
    )
    (net (code "192") (name "unconnected-(IC1-IO_L18P_T2_D28_14-PadR11)") (class "Default")
      (node (ref "IC1") (pin "R11") (pinfunction "IO_L18P_T2_D28_14_R11") (pintype "bidirectional"))
    )
    (net (code "193") (name "unconnected-(IC1-IO_L19N_T3_D25_VREF_14-PadM8)") (class "Default")
      (node (ref "IC1") (pin "M8") (pinfunction "IO_L19N_T3_D25_VREF_14_M8") (pintype "bidirectional"))
    )
    (net (code "194") (name "unconnected-(IC1-IO_L19N_T3_VREF_15-PadD15)") (class "Default")
      (node (ref "IC1") (pin "D15") (pinfunction "IO_L19N_T3_VREF_15_D15") (pintype "bidirectional"))
    )
    (net (code "195") (name "unconnected-(IC1-IO_L19N_T3_VREF_34-PadM3)") (class "Default")
      (node (ref "IC1") (pin "M3") (pinfunction "IO_L19N_T3_VREF_34_M3") (pintype "bidirectional"))
    )
    (net (code "196") (name "unconnected-(IC1-IO_L19P_T3_15-PadE14)") (class "Default")
      (node (ref "IC1") (pin "E14") (pinfunction "IO_L19P_T3_15_E14") (pintype "bidirectional"))
    )
    (net (code "197") (name "unconnected-(IC1-IO_L19P_T3_34-PadM4)") (class "Default")
      (node (ref "IC1") (pin "M4") (pinfunction "IO_L19P_T3_34_M4") (pintype "bidirectional"))
    )
    (net (code "198") (name "unconnected-(IC1-IO_L19P_T3_D26_14-PadM7)") (class "Default")
      (node (ref "IC1") (pin "M7") (pinfunction "IO_L19P_T3_D26_14_M7") (pintype "bidirectional"))
    )
    (net (code "199") (name "unconnected-(IC1-IO_L20N_T3_15-PadF15)") (class "Default")
      (node (ref "IC1") (pin "F15") (pinfunction "IO_L20N_T3_15_F15") (pintype "bidirectional"))
    )
    (net (code "200") (name "unconnected-(IC1-IO_L20N_T3_34-PadM2)") (class "Default")
      (node (ref "IC1") (pin "M2") (pinfunction "IO_L20N_T3_34_M2") (pintype "bidirectional"))
    )
    (net (code "201") (name "unconnected-(IC1-IO_L20N_T3_D23_14-PadN7)") (class "Default")
      (node (ref "IC1") (pin "N7") (pinfunction "IO_L20N_T3_D23_14_N7") (pintype "bidirectional"))
    )
    (net (code "202") (name "unconnected-(IC1-IO_L20P_T3_15-PadG15)") (class "Default")
      (node (ref "IC1") (pin "G15") (pinfunction "IO_L20P_T3_15_G15") (pintype "bidirectional"))
    )
    (net (code "203") (name "unconnected-(IC1-IO_L20P_T3_34-PadN2)") (class "Default")
      (node (ref "IC1") (pin "N2") (pinfunction "IO_L20P_T3_34_N2") (pintype "bidirectional"))
    )
    (net (code "204") (name "unconnected-(IC1-IO_L20P_T3_D24_14-PadN6)") (class "Default")
      (node (ref "IC1") (pin "N6") (pinfunction "IO_L20P_T3_D24_14_N6") (pintype "bidirectional"))
    )
    (net (code "205") (name "unconnected-(IC1-IO_L21N_T3_DQS_15-PadE15)") (class "Default")
      (node (ref "IC1") (pin "E15") (pinfunction "IO_L21N_T3_DQS_15_E15") (pintype "bidirectional"))
    )
    (net (code "206") (name "unconnected-(IC1-IO_L21N_T3_DQS_34-PadN3)") (class "Default")
      (node (ref "IC1") (pin "N3") (pinfunction "IO_L21N_T3_DQS_34_N3") (pintype "bidirectional"))
    )
    (net (code "207") (name "unconnected-(IC1-IO_L21N_T3_DQS_D22_14-PadN9)") (class "Default")
      (node (ref "IC1") (pin "N9") (pinfunction "IO_L21N_T3_DQS_D22_14_N9") (pintype "bidirectional"))
    )
    (net (code "208") (name "unconnected-(IC1-IO_L21P_T3_DQS_14-PadN8)") (class "Default")
      (node (ref "IC1") (pin "N8") (pinfunction "IO_L21P_T3_DQS_14_N8") (pintype "bidirectional"))
    )
    (net (code "209") (name "unconnected-(IC1-IO_L21P_T3_DQS_15-PadF14)") (class "Default")
      (node (ref "IC1") (pin "F14") (pinfunction "IO_L21P_T3_DQS_15_F14") (pintype "bidirectional"))
    )
    (net (code "210") (name "unconnected-(IC1-IO_L21P_T3_DQS_34-PadP3)") (class "Default")
      (node (ref "IC1") (pin "P3") (pinfunction "IO_L21P_T3_DQS_34_P3") (pintype "bidirectional"))
    )
    (net (code "211") (name "unconnected-(IC1-IO_L22N_T3_15-PadG14)") (class "Default")
      (node (ref "IC1") (pin "G14") (pinfunction "IO_L22N_T3_15_G14") (pintype "bidirectional"))
    )
    (net (code "212") (name "unconnected-(IC1-IO_L22N_T3_34-PadN1)") (class "Default")
      (node (ref "IC1") (pin "N1") (pinfunction "IO_L22N_T3_34_N1") (pintype "bidirectional"))
    )
    (net (code "213") (name "unconnected-(IC1-IO_L22N_T3_D20_14-PadR8)") (class "Default")
      (node (ref "IC1") (pin "R8") (pinfunction "IO_L22N_T3_D20_14_R8") (pintype "bidirectional"))
    )
    (net (code "214") (name "unconnected-(IC1-IO_L22P_T3_15-PadG13)") (class "Default")
      (node (ref "IC1") (pin "G13") (pinfunction "IO_L22P_T3_15_G13") (pintype "bidirectional"))
    )
    (net (code "215") (name "unconnected-(IC1-IO_L22P_T3_34-PadP1)") (class "Default")
      (node (ref "IC1") (pin "P1") (pinfunction "IO_L22P_T3_34_P1") (pintype "bidirectional"))
    )
    (net (code "216") (name "unconnected-(IC1-IO_L22P_T3_D21_14-PadR7)") (class "Default")
      (node (ref "IC1") (pin "R7") (pinfunction "IO_L22P_T3_D21_14_R7") (pintype "bidirectional"))
    )
    (net (code "217") (name "unconnected-(IC1-IO_L23N_T3_15-PadG12)") (class "Default")
      (node (ref "IC1") (pin "G12") (pinfunction "IO_L23N_T3_15_G12") (pintype "bidirectional"))
    )
    (net (code "218") (name "unconnected-(IC1-IO_L23N_T3_34-PadR3)") (class "Default")
      (node (ref "IC1") (pin "R3") (pinfunction "IO_L23N_T3_34_R3") (pintype "bidirectional"))
    )
    (net (code "219") (name "unconnected-(IC1-IO_L23N_T3_D18_14-PadP7)") (class "Default")
      (node (ref "IC1") (pin "P7") (pinfunction "IO_L23N_T3_D18_14_P7") (pintype "bidirectional"))
    )
    (net (code "220") (name "unconnected-(IC1-IO_L23P_T3_15-PadG11)") (class "Default")
      (node (ref "IC1") (pin "G11") (pinfunction "IO_L23P_T3_15_G11") (pintype "bidirectional"))
    )
    (net (code "221") (name "unconnected-(IC1-IO_L23P_T3_34-PadR4)") (class "Default")
      (node (ref "IC1") (pin "R4") (pinfunction "IO_L23P_T3_34_R4") (pintype "bidirectional"))
    )
    (net (code "222") (name "unconnected-(IC1-IO_L23P_T3_D19_14-PadP6)") (class "Default")
      (node (ref "IC1") (pin "P6") (pinfunction "IO_L23P_T3_D19_14_P6") (pintype "bidirectional"))
    )
    (net (code "223") (name "unconnected-(IC1-IO_L24N_T3_34-PadP2)") (class "Default")
      (node (ref "IC1") (pin "P2") (pinfunction "IO_L24N_T3_34_P2") (pintype "bidirectional"))
    )
    (net (code "224") (name "unconnected-(IC1-IO_L24N_T3_D16_14-PadR6)") (class "Default")
      (node (ref "IC1") (pin "R6") (pinfunction "IO_L24N_T3_D16_14_R6") (pintype "bidirectional"))
    )
    (net (code "225") (name "unconnected-(IC1-IO_L24N_T3_RS0_15-PadH13)") (class "Default")
      (node (ref "IC1") (pin "H13") (pinfunction "IO_L24N_T3_RS0_15_H13") (pintype "bidirectional"))
    )
    (net (code "226") (name "unconnected-(IC1-IO_L24P_T3_34-PadR2)") (class "Default")
      (node (ref "IC1") (pin "R2") (pinfunction "IO_L24P_T3_34_R2") (pintype "bidirectional"))
    )
    (net (code "227") (name "unconnected-(IC1-IO_L24P_T3_D17_14-PadR5)") (class "Default")
      (node (ref "IC1") (pin "R5") (pinfunction "IO_L24P_T3_D17_14_R5") (pintype "bidirectional"))
    )
    (net (code "228") (name "unconnected-(IC1-IO_L24P_T3_RS1_15-PadH12)") (class "Default")
      (node (ref "IC1") (pin "H12") (pinfunction "IO_L24P_T3_RS1_15_H12") (pintype "bidirectional"))
    )
    (net (code "229") (name "unconnected-(JP1-Pad12)") (class "Default")
      (node (ref "JP1") (pin "12") (pinfunction "12_12") (pintype "passive"))
    )
    (net (code "230") (name "unconnected-(JP1-Pad14)") (class "Default")
      (node (ref "JP1") (pin "14") (pinfunction "14_14") (pintype "passive"))
    )
    (net (code "231") (name "unconnected-(Q1-C{slash}-Pad2@1)") (class "Default")
      (node (ref "Q1") (pin "2@1") (pinfunction "C/_2@1") (pintype "passive"))
    )
    (net (code "232") (name "unconnected-(Q2-C{slash}-Pad2@1)") (class "Default")
      (node (ref "Q2") (pin "2@1") (pinfunction "C/_2@1") (pintype "passive"))
    )
    (net (code "233") (name "unconnected-(Q3-C{slash}-Pad2@1)") (class "Default")
      (node (ref "Q3") (pin "2@1") (pinfunction "C/_2@1") (pintype "passive"))
    )
  )
)
